# test-board.net
KiCad netlist of a schematic drawn in EAGLE
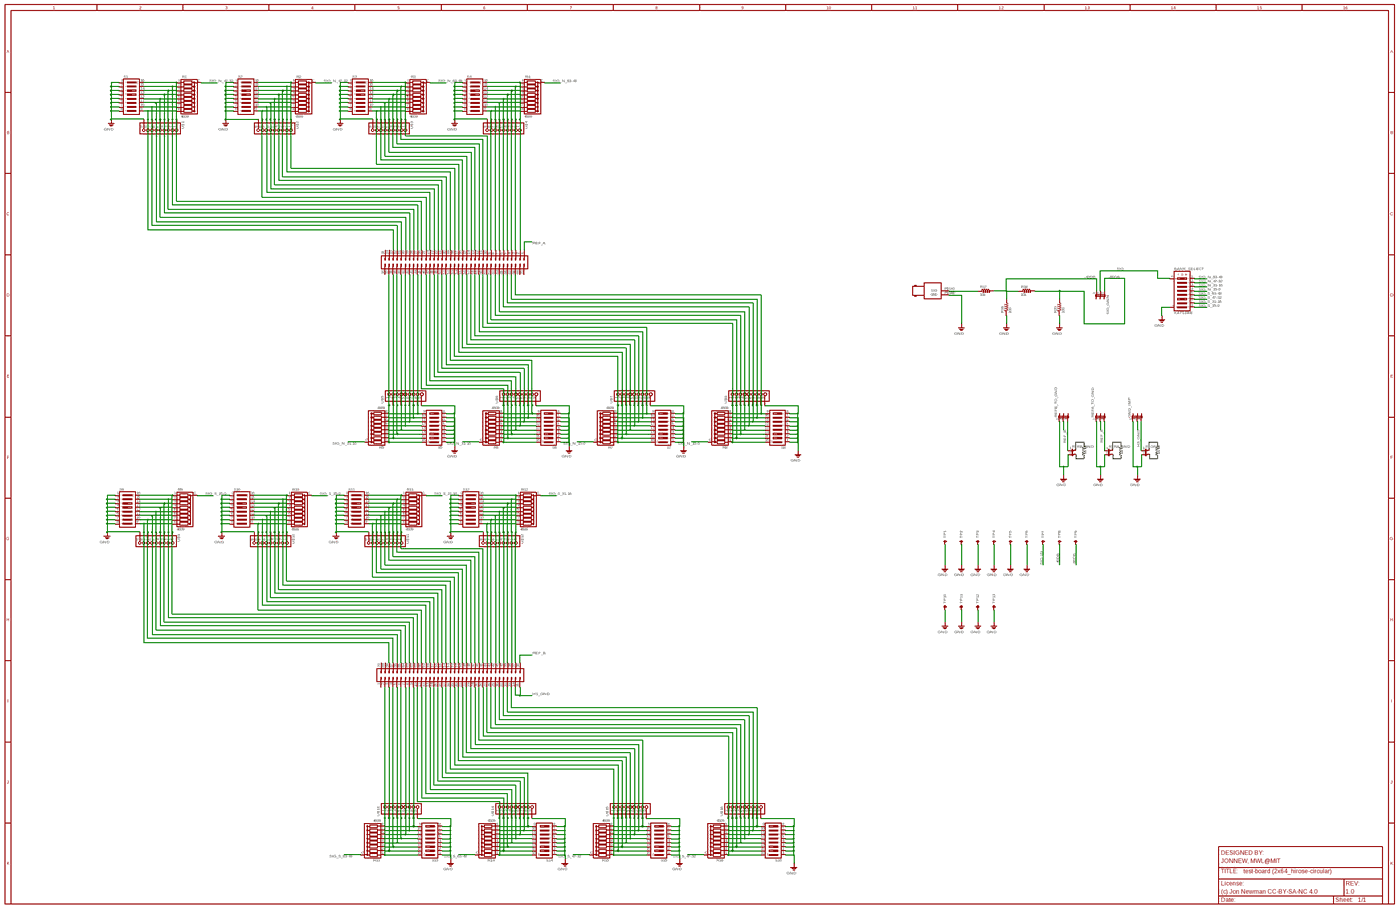
[diagram p0: schematic, sheet 1, overview]
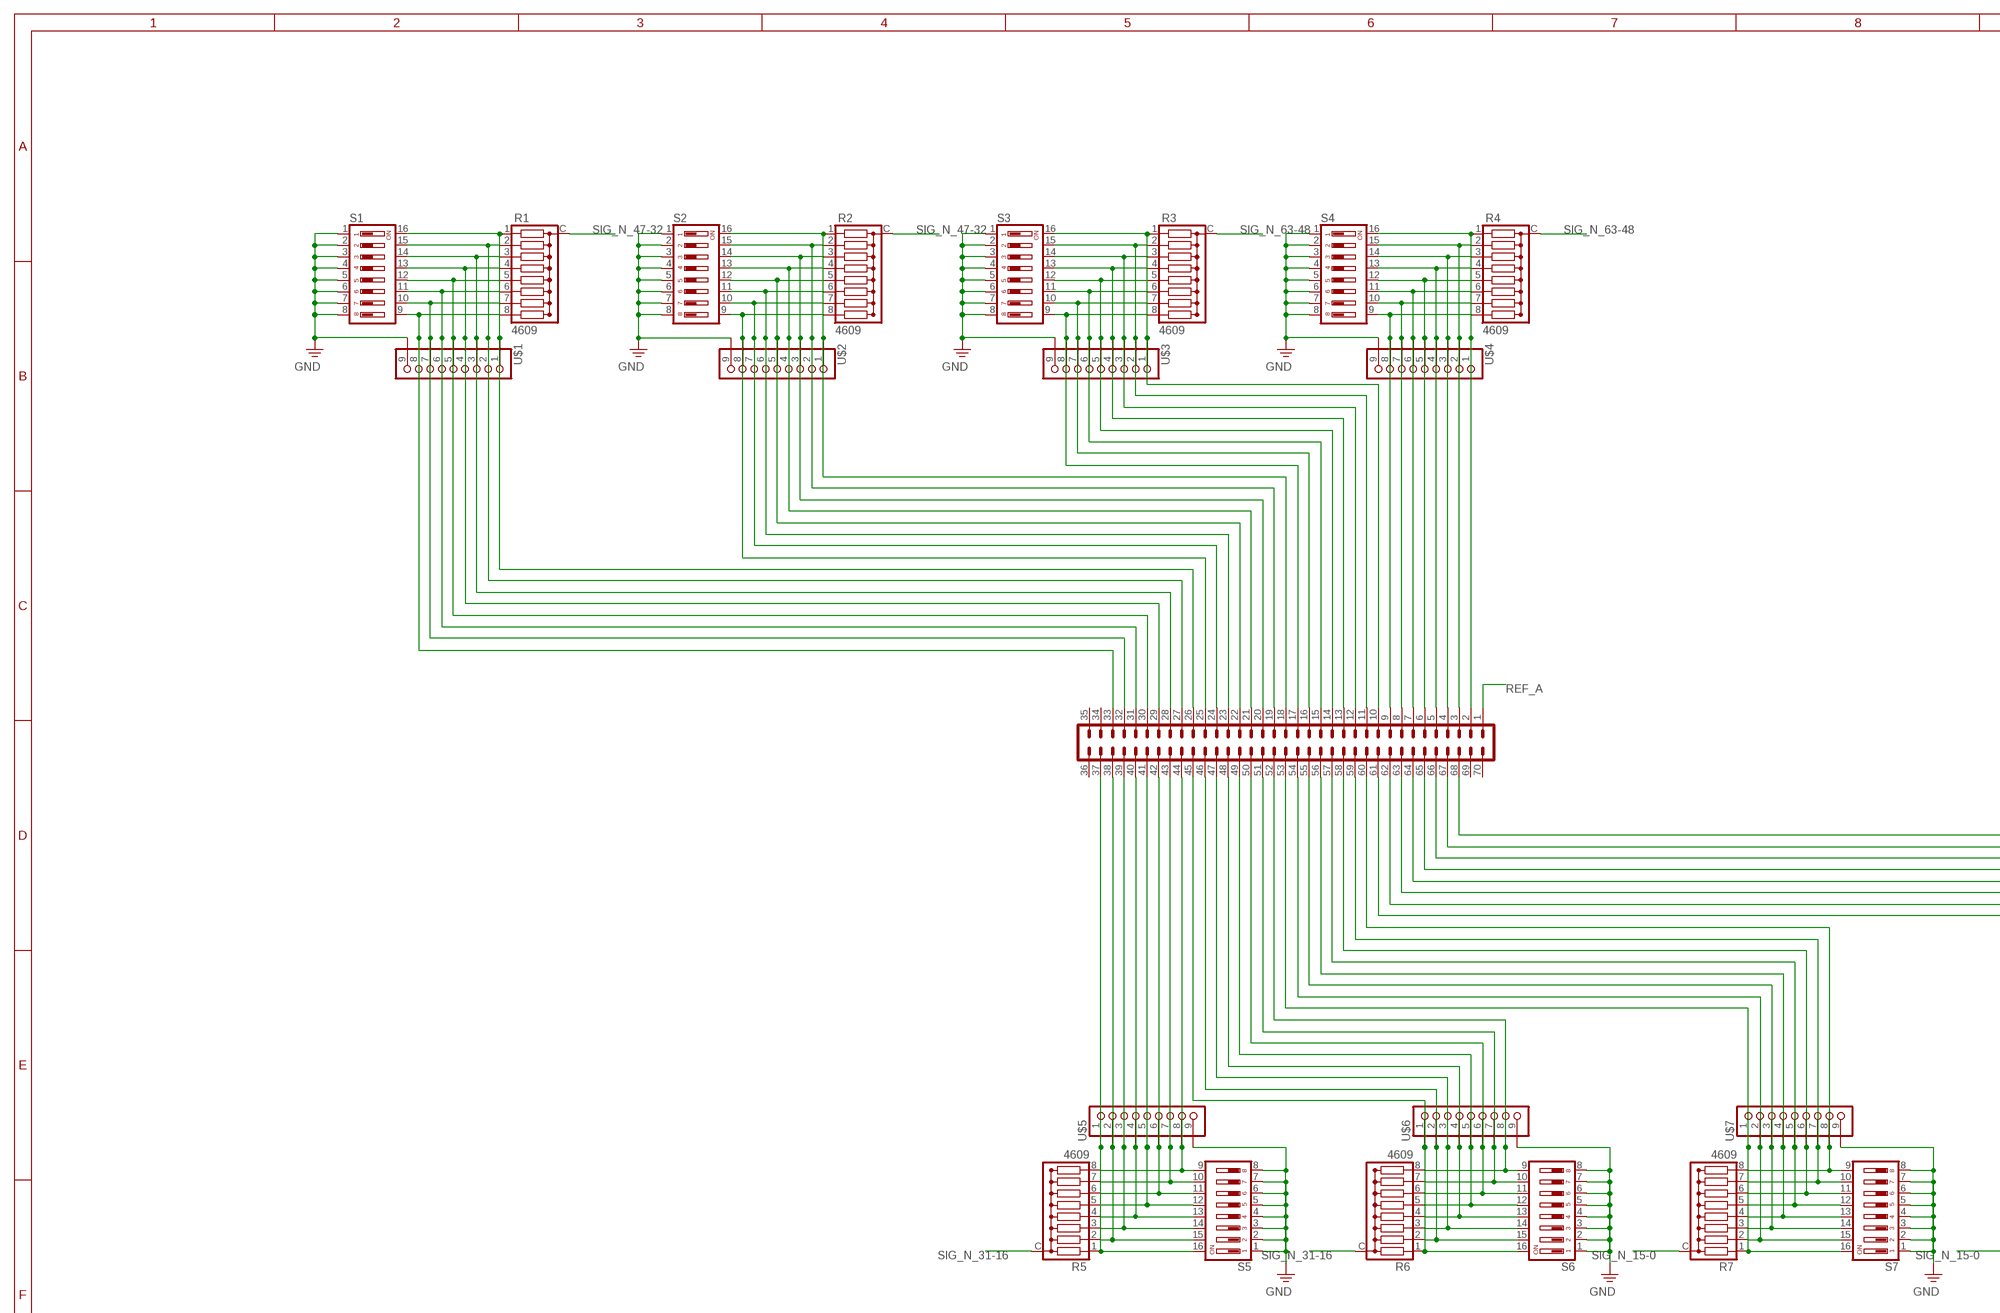
[diagram p1: schematic, sheet 1, part 1 of 4]
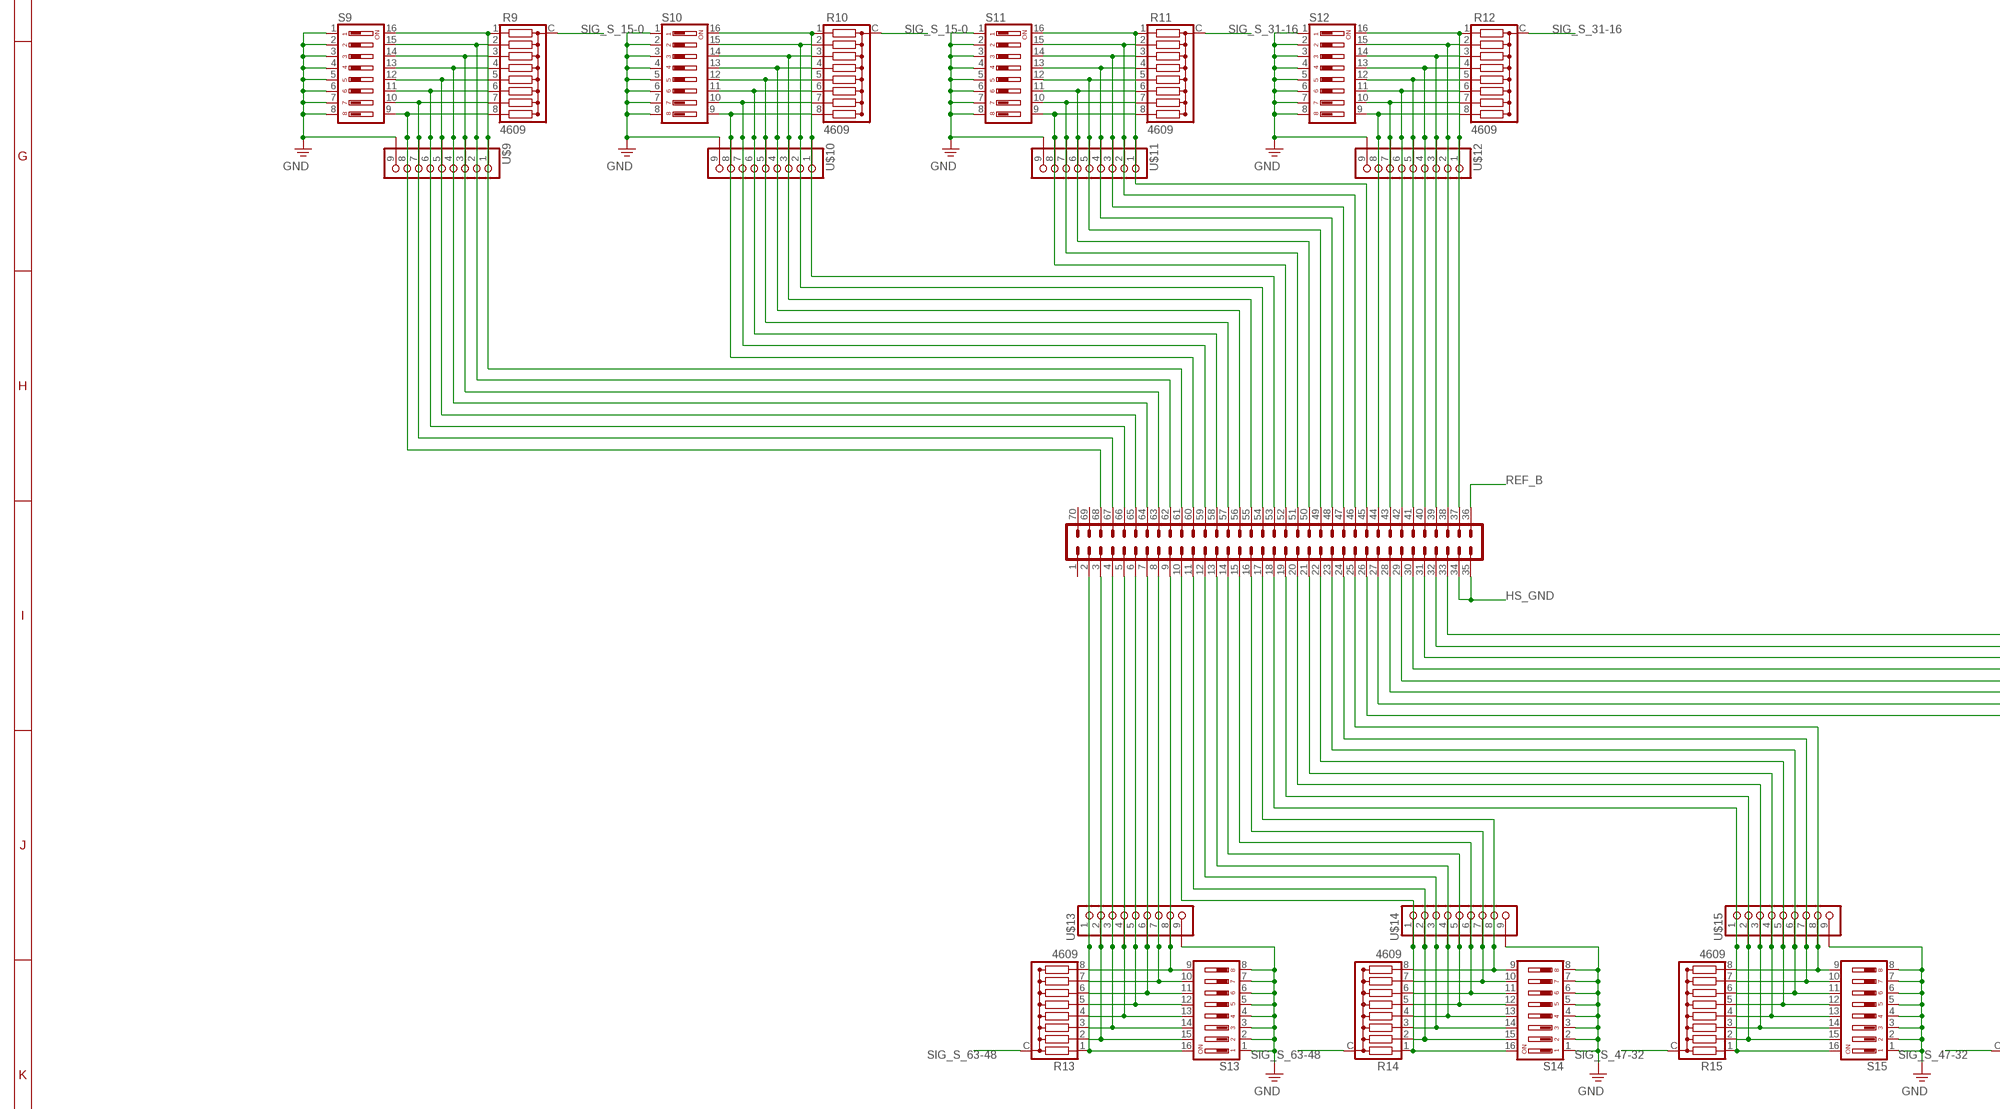
[diagram p2: schematic, sheet 1, part 2 of 4]
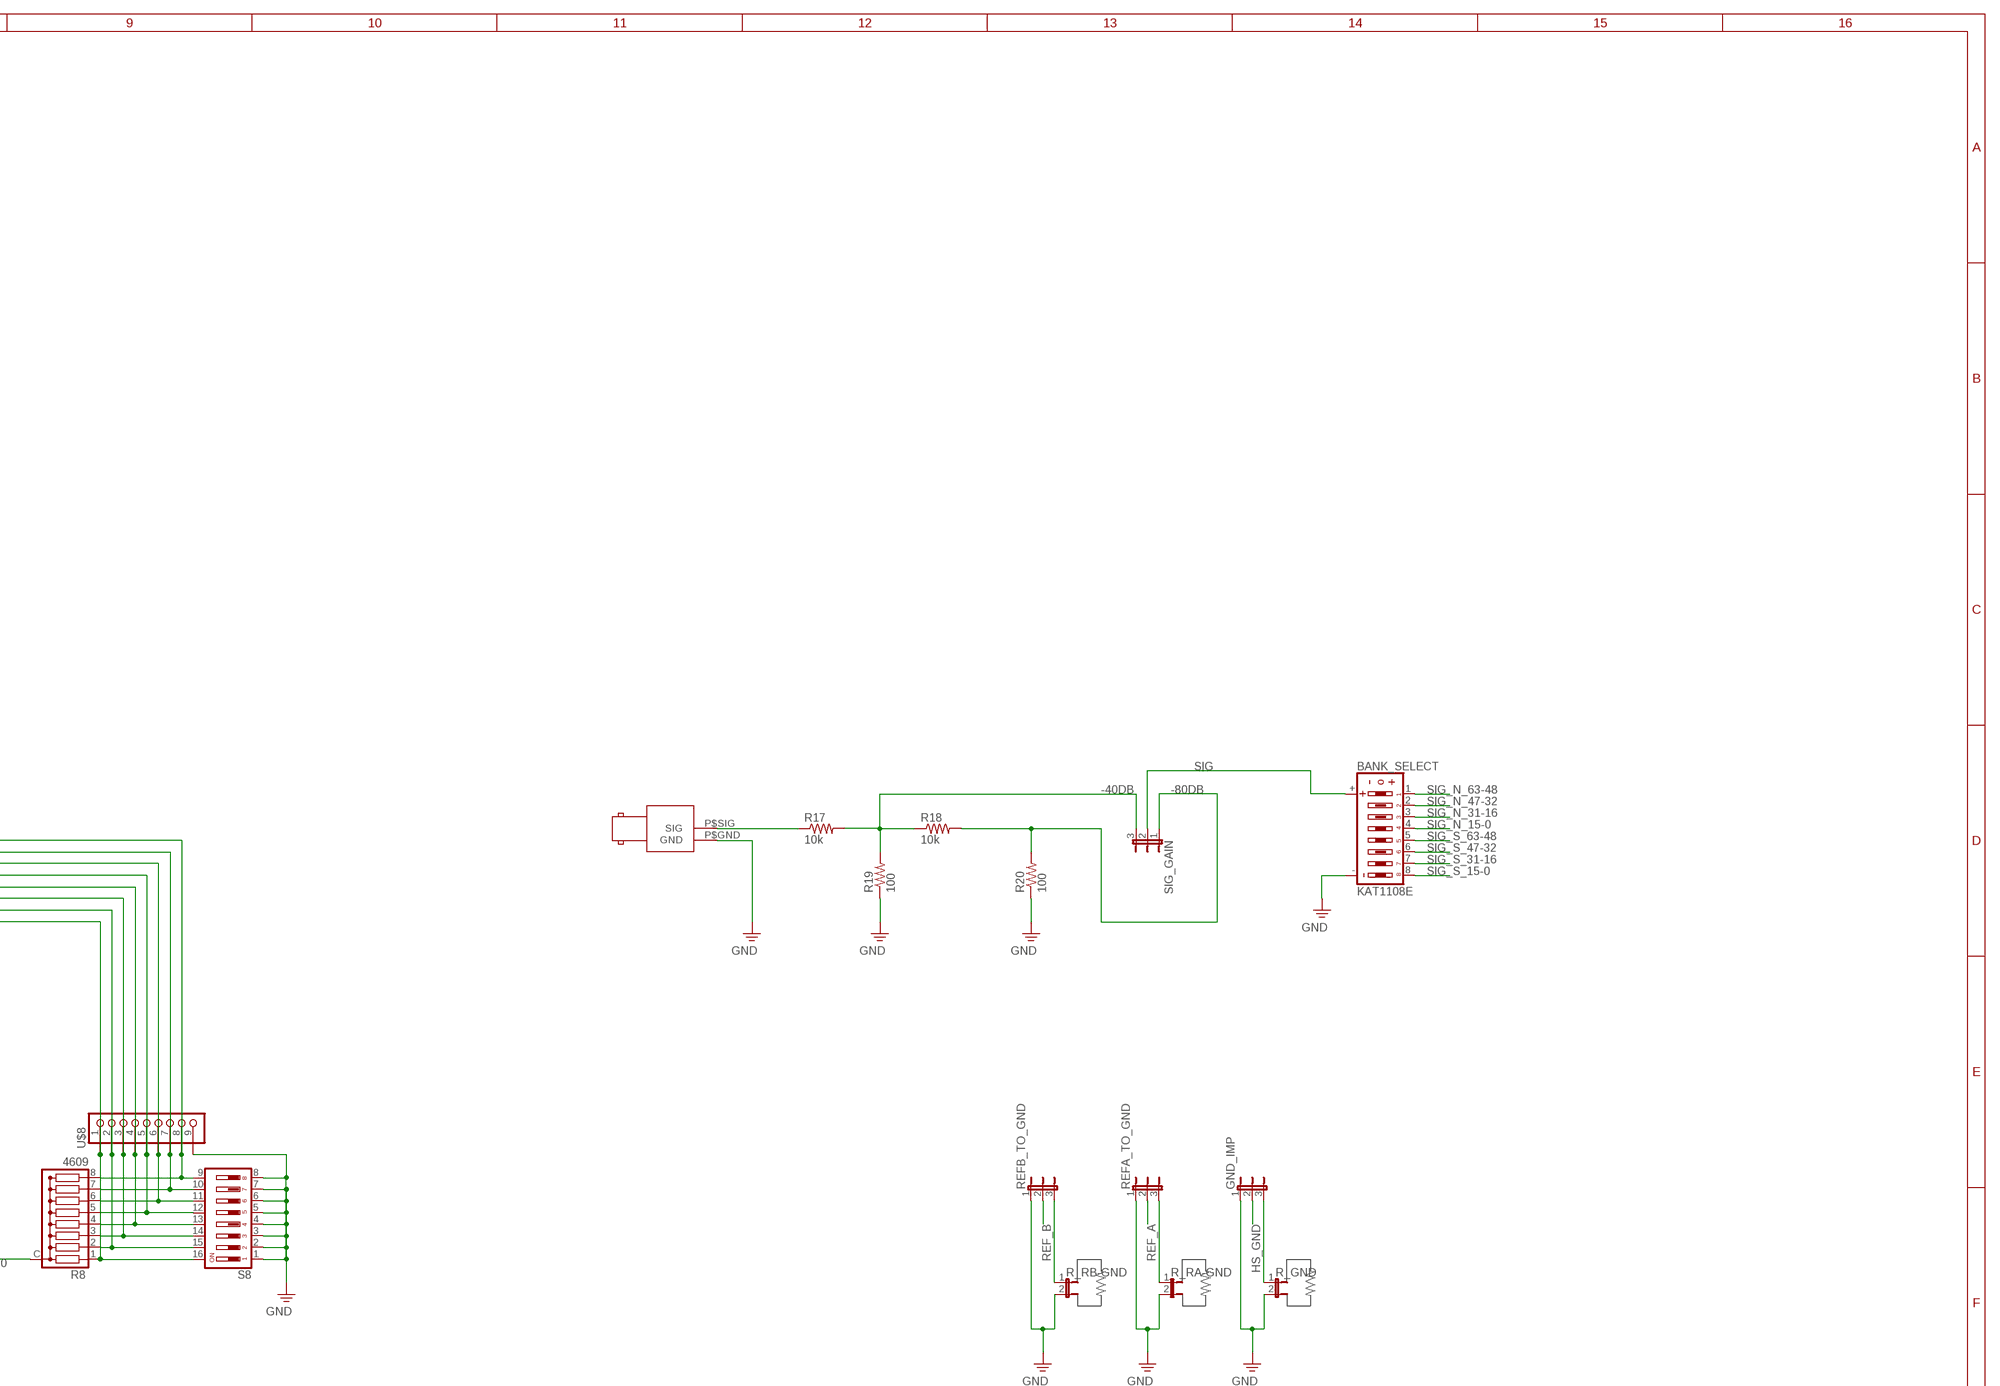
[diagram p3: schematic, sheet 1, part 3 of 4]
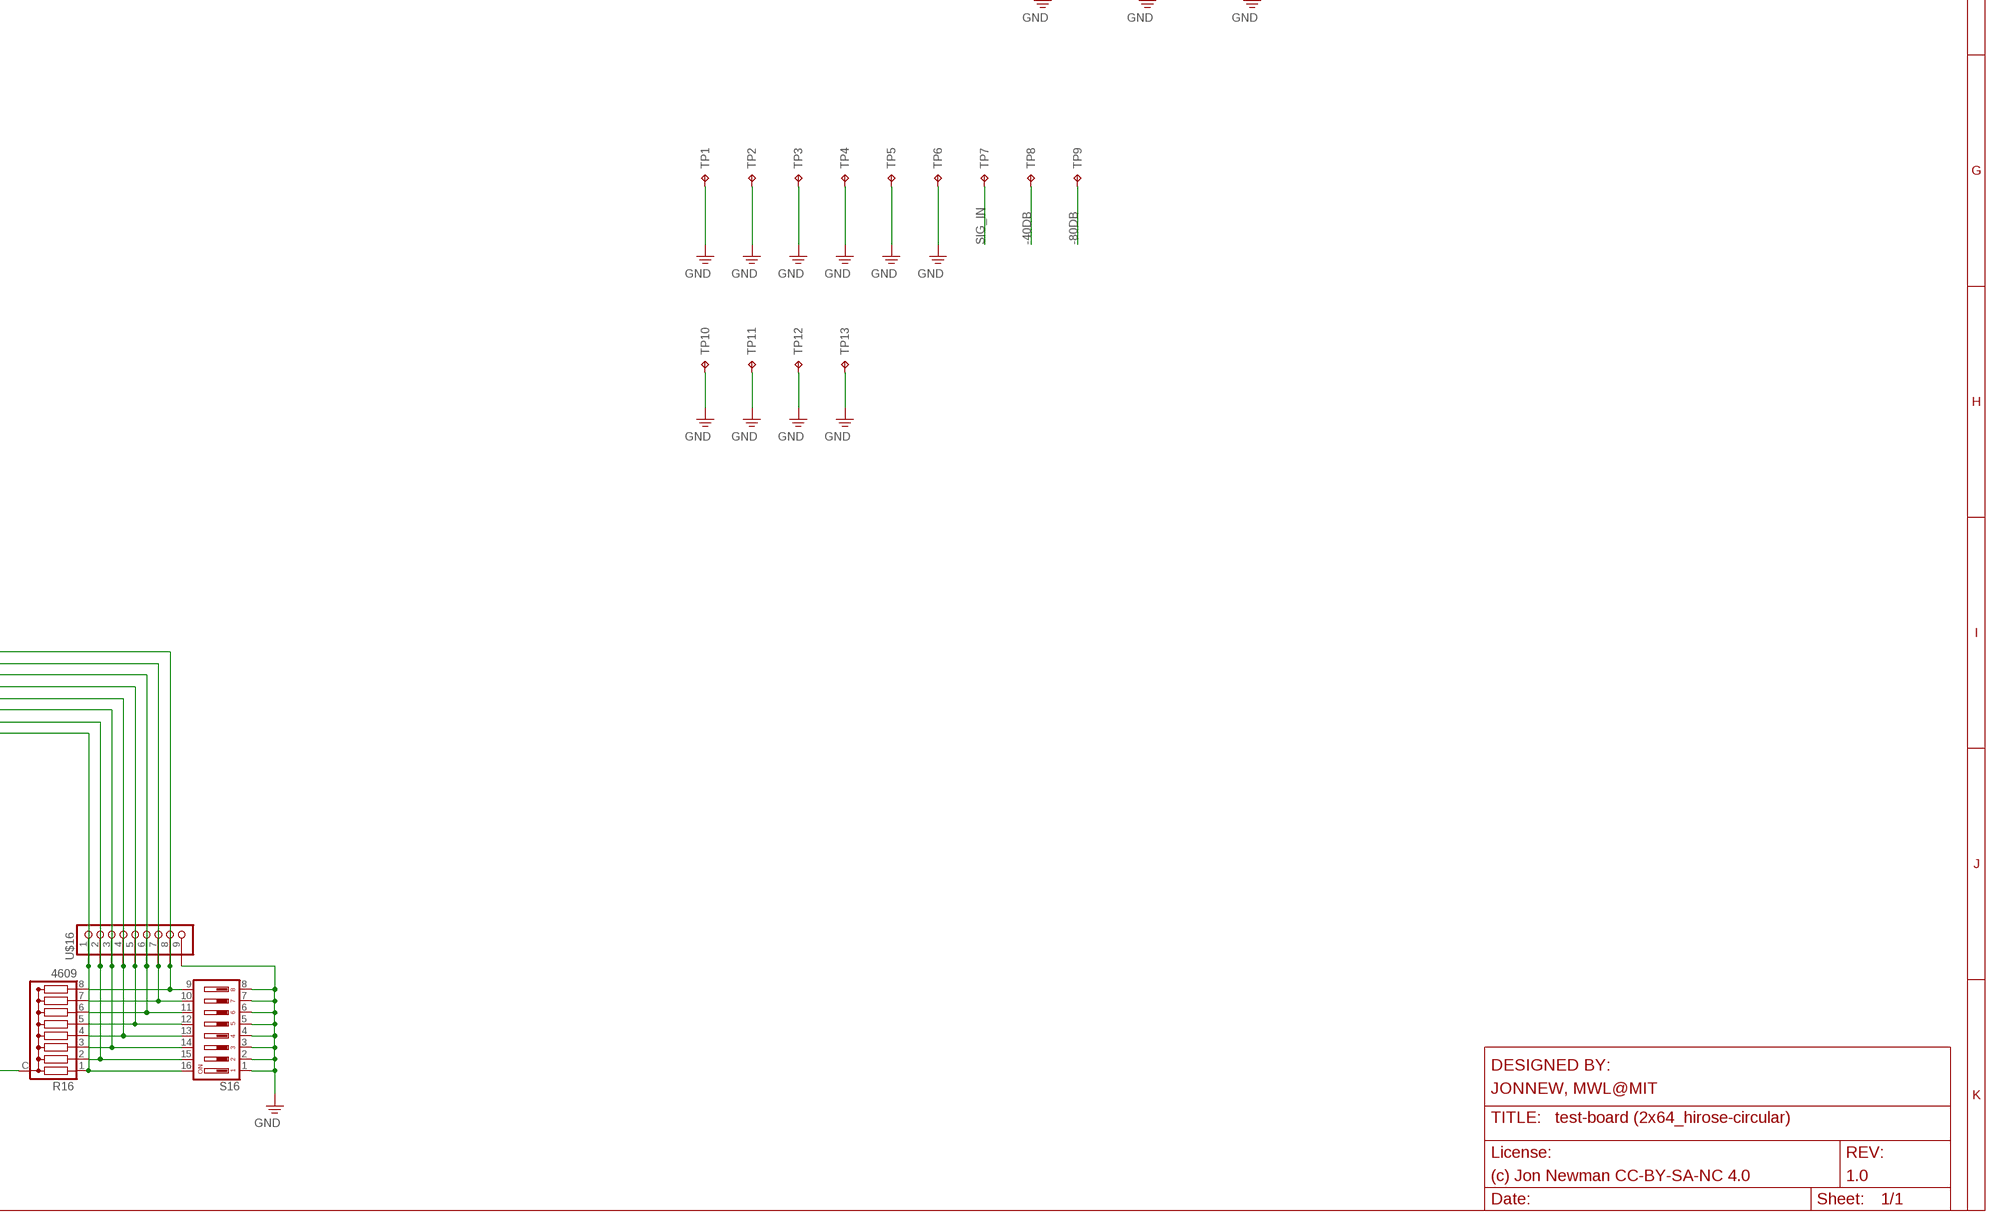
[diagram p4: schematic, sheet 1, part 4 of 4]

(export (version "E")
  (design (tool "Eeschema 10.0.6"))
  (components
    (comp (ref "AIN_N0T")
      (value "DF40HEAD")
      (footprint "eagle-import:DF40-70HEAD")
      (libsource (lib "eagle-import") (part "PINHD-2X35_DF40HEAD"))
    )
    (comp (ref "AIN_S0T")
      (value "DF40HEAD")
      (footprint "eagle-import:DF40-70HEAD")
      (libsource (lib "eagle-import") (part "PINHD-2X35_DF40HEAD"))
    )
    (comp (ref "BANK_SELECT")
      (value "KAT1108E")
      (footprint "eagle-import:206-124_DIP8-SPDT")
      (libsource (lib "eagle-import") (part "DIPSW-008-SPDT_206-124"))
    )
    (comp (ref "GND_IMP")
      (value "JP3E")
      (footprint "eagle-import:JP3")
      (libsource (lib "eagle-import") (part "JP3E"))
    )
    (comp (ref "R1")
      (value "4609")
      (footprint "eagle-import:RNX8-0.1")
      (libsource (lib "eagle-import") (part "RN1X8"))
    )
    (comp (ref "R2")
      (value "4609")
      (footprint "eagle-import:RNX8-0.1")
      (libsource (lib "eagle-import") (part "RN1X8"))
    )
    (comp (ref "R3")
      (value "4609")
      (footprint "eagle-import:RNX8-0.1")
      (libsource (lib "eagle-import") (part "RN1X8"))
    )
    (comp (ref "R4")
      (value "4609")
      (footprint "eagle-import:RNX8-0.1")
      (libsource (lib "eagle-import") (part "RN1X8"))
    )
    (comp (ref "R5")
      (value "4609")
      (footprint "eagle-import:RNX8-0.1")
      (libsource (lib "eagle-import") (part "RN1X8"))
    )
    (comp (ref "R6")
      (value "4609")
      (footprint "eagle-import:RNX8-0.1")
      (libsource (lib "eagle-import") (part "RN1X8"))
    )
    (comp (ref "R7")
      (value "4609")
      (footprint "eagle-import:RNX8-0.1")
      (libsource (lib "eagle-import") (part "RN1X8"))
    )
    (comp (ref "R8")
      (value "4609")
      (footprint "eagle-import:RNX8-0.1")
      (libsource (lib "eagle-import") (part "RN1X8"))
    )
    (comp (ref "R9")
      (value "4609")
      (footprint "eagle-import:RNX8-0.1")
      (libsource (lib "eagle-import") (part "RN1X8"))
    )
    (comp (ref "R10")
      (value "4609")
      (footprint "eagle-import:RNX8-0.1")
      (libsource (lib "eagle-import") (part "RN1X8"))
    )
    (comp (ref "R11")
      (value "4609")
      (footprint "eagle-import:RNX8-0.1")
      (libsource (lib "eagle-import") (part "RN1X8"))
    )
    (comp (ref "R12")
      (value "4609")
      (footprint "eagle-import:RNX8-0.1")
      (libsource (lib "eagle-import") (part "RN1X8"))
    )
    (comp (ref "R13")
      (value "4609")
      (footprint "eagle-import:RNX8-0.1")
      (libsource (lib "eagle-import") (part "RN1X8"))
    )
    (comp (ref "R14")
      (value "4609")
      (footprint "eagle-import:RNX8-0.1")
      (libsource (lib "eagle-import") (part "RN1X8"))
    )
    (comp (ref "R15")
      (value "4609")
      (footprint "eagle-import:RNX8-0.1")
      (libsource (lib "eagle-import") (part "RN1X8"))
    )
    (comp (ref "R16")
      (value "4609")
      (footprint "eagle-import:RNX8-0.1")
      (libsource (lib "eagle-import") (part "RN1X8"))
    )
    (comp (ref "R17")
      (value "10k")
      (footprint "eagle-import:0805")
      (libsource (lib "eagle-import") (part "R_0805"))
    )
    (comp (ref "R18")
      (value "10k")
      (footprint "eagle-import:0805")
      (libsource (lib "eagle-import") (part "R_0805"))
    )
    (comp (ref "R19")
      (value "100")
      (footprint "eagle-import:0805")
      (libsource (lib "eagle-import") (part "R_0805"))
    )
    (comp (ref "R20")
      (value "100")
      (footprint "eagle-import:0805")
      (libsource (lib "eagle-import") (part "R_0805"))
    )
    (comp (ref "REFA_TO_GND")
      (value "JP3E")
      (footprint "eagle-import:JP3")
      (libsource (lib "eagle-import") (part "JP3E"))
    )
    (comp (ref "REFB_TO_GND")
      (value "JP3E")
      (footprint "eagle-import:JP3")
      (libsource (lib "eagle-import") (part "JP3E"))
    )
    (comp (ref "R_GND")
      (value "JP2E_THRU-HOLE")
      (footprint "eagle-import:JP2")
      (libsource (lib "eagle-import") (part "JP2E_THRU-HOLE"))
    )
    (comp (ref "R_RA-GND")
      (value "JP2E_THRU-HOLE")
      (footprint "eagle-import:JP2")
      (libsource (lib "eagle-import") (part "JP2E_THRU-HOLE"))
    )
    (comp (ref "R_RB-GND")
      (value "JP2E_THRU-HOLE")
      (footprint "eagle-import:JP2")
      (libsource (lib "eagle-import") (part "JP2E_THRU-HOLE"))
    )
    (comp (ref "S1")
      (value "DIPSW-008_ADE")
      (footprint "eagle-import:ADE_DIP8-SPST")
      (libsource (lib "eagle-import") (part "DIPSW-008_ADE"))
    )
    (comp (ref "S2")
      (value "DIPSW-008_ADE")
      (footprint "eagle-import:ADE_DIP8-SPST")
      (libsource (lib "eagle-import") (part "DIPSW-008_ADE"))
    )
    (comp (ref "S3")
      (value "DIPSW-008_ADE")
      (footprint "eagle-import:ADE_DIP8-SPST")
      (libsource (lib "eagle-import") (part "DIPSW-008_ADE"))
    )
    (comp (ref "S4")
      (value "DIPSW-008_ADE")
      (footprint "eagle-import:ADE_DIP8-SPST")
      (libsource (lib "eagle-import") (part "DIPSW-008_ADE"))
    )
    (comp (ref "S5")
      (value "DIPSW-008_ADE")
      (footprint "eagle-import:ADE_DIP8-SPST")
      (libsource (lib "eagle-import") (part "DIPSW-008_ADE"))
    )
    (comp (ref "S6")
      (value "DIPSW-008_ADE")
      (footprint "eagle-import:ADE_DIP8-SPST")
      (libsource (lib "eagle-import") (part "DIPSW-008_ADE"))
    )
    (comp (ref "S7")
      (value "DIPSW-008_ADE")
      (footprint "eagle-import:ADE_DIP8-SPST")
      (libsource (lib "eagle-import") (part "DIPSW-008_ADE"))
    )
    (comp (ref "S8")
      (value "DIPSW-008_ADE")
      (footprint "eagle-import:ADE_DIP8-SPST")
      (libsource (lib "eagle-import") (part "DIPSW-008_ADE"))
    )
    (comp (ref "S9")
      (value "DIPSW-008_ADE")
      (footprint "eagle-import:ADE_DIP8-SPST")
      (libsource (lib "eagle-import") (part "DIPSW-008_ADE"))
    )
    (comp (ref "S10")
      (value "DIPSW-008_ADE")
      (footprint "eagle-import:ADE_DIP8-SPST")
      (libsource (lib "eagle-import") (part "DIPSW-008_ADE"))
    )
    (comp (ref "S11")
      (value "DIPSW-008_ADE")
      (footprint "eagle-import:ADE_DIP8-SPST")
      (libsource (lib "eagle-import") (part "DIPSW-008_ADE"))
    )
    (comp (ref "S12")
      (value "DIPSW-008_ADE")
      (footprint "eagle-import:ADE_DIP8-SPST")
      (libsource (lib "eagle-import") (part "DIPSW-008_ADE"))
    )
    (comp (ref "S13")
      (value "DIPSW-008_ADE")
      (footprint "eagle-import:ADE_DIP8-SPST")
      (libsource (lib "eagle-import") (part "DIPSW-008_ADE"))
    )
    (comp (ref "S14")
      (value "DIPSW-008_ADE")
      (footprint "eagle-import:ADE_DIP8-SPST")
      (libsource (lib "eagle-import") (part "DIPSW-008_ADE"))
    )
    (comp (ref "S15")
      (value "DIPSW-008_ADE")
      (footprint "eagle-import:ADE_DIP8-SPST")
      (libsource (lib "eagle-import") (part "DIPSW-008_ADE"))
    )
    (comp (ref "S16")
      (value "DIPSW-008_ADE")
      (footprint "eagle-import:ADE_DIP8-SPST")
      (libsource (lib "eagle-import") (part "DIPSW-008_ADE"))
    )
    (comp (ref "SIG_GAIN")
      (value "JP3E")
      (footprint "eagle-import:JP3")
      (libsource (lib "eagle-import") (part "JP3E"))
    )
    (comp (ref "SIG_IN")
      (value "1-1634622-0")
      (footprint "eagle-import:BNC_RIGHT_ANGLE")
      (libsource (lib "eagle-import") (part "BNC_RIGHT_ANGLE"))
    )
    (comp (ref "TP1")
      (value "GND")
      (footprint "eagle-import:P1-20")
      (libsource (lib "eagle-import") (part "TPPAD1-20"))
    )
    (comp (ref "TP2")
      (value "GND")
      (footprint "eagle-import:P1-20")
      (libsource (lib "eagle-import") (part "TPPAD1-20"))
    )
    (comp (ref "TP3")
      (value "GND")
      (footprint "eagle-import:P1-20")
      (libsource (lib "eagle-import") (part "TPPAD1-20"))
    )
    (comp (ref "TP4")
      (value "GND")
      (footprint "eagle-import:P1-20")
      (libsource (lib "eagle-import") (part "TPPAD1-20"))
    )
    (comp (ref "TP5")
      (value "GND")
      (footprint "eagle-import:P1-20")
      (libsource (lib "eagle-import") (part "TPPAD1-20"))
    )
    (comp (ref "TP6")
      (value "GND")
      (footprint "eagle-import:P1-20")
      (libsource (lib "eagle-import") (part "TPPAD1-20"))
    )
    (comp (ref "TP7")
      (value "SIG_IN")
      (footprint "eagle-import:P1-20")
      (libsource (lib "eagle-import") (part "TPPAD1-20"))
    )
    (comp (ref "TP8")
      (value "-40dB")
      (footprint "eagle-import:P1-20")
      (libsource (lib "eagle-import") (part "TPPAD1-20"))
    )
    (comp (ref "TP9")
      (value "-80dB")
      (footprint "eagle-import:P1-20")
      (libsource (lib "eagle-import") (part "TPPAD1-20"))
    )
    (comp (ref "TP10")
      (value "TP_4-40")
      (footprint "eagle-import:4-40_PLATED")
      (libsource (lib "eagle-import") (part "TP_4-40"))
    )
    (comp (ref "TP11")
      (value "TP_4-40")
      (footprint "eagle-import:4-40_PLATED")
      (libsource (lib "eagle-import") (part "TP_4-40"))
    )
    (comp (ref "TP12")
      (value "TP_4-40")
      (footprint "eagle-import:4-40_PLATED")
      (libsource (lib "eagle-import") (part "TP_4-40"))
    )
    (comp (ref "TP13")
      (value "TP_4-40")
      (footprint "eagle-import:4-40_PLATED")
      (libsource (lib "eagle-import") (part "TP_4-40"))
    )
    (comp (ref "U$1")
      (value "PINHD-1X9")
      (footprint "eagle-import:1X09")
      (libsource (lib "eagle-import") (part "PINHD-1X9"))
    )
    (comp (ref "U$2")
      (value "PINHD-1X9")
      (footprint "eagle-import:1X09")
      (libsource (lib "eagle-import") (part "PINHD-1X9"))
    )
    (comp (ref "U$3")
      (value "PINHD-1X9")
      (footprint "eagle-import:1X09")
      (libsource (lib "eagle-import") (part "PINHD-1X9"))
    )
    (comp (ref "U$4")
      (value "PINHD-1X9")
      (footprint "eagle-import:1X09")
      (libsource (lib "eagle-import") (part "PINHD-1X9"))
    )
    (comp (ref "U$5")
      (value "PINHD-1X9")
      (footprint "eagle-import:1X09")
      (libsource (lib "eagle-import") (part "PINHD-1X9"))
    )
    (comp (ref "U$6")
      (value "PINHD-1X9")
      (footprint "eagle-import:1X09")
      (libsource (lib "eagle-import") (part "PINHD-1X9"))
    )
    (comp (ref "U$7")
      (value "PINHD-1X9")
      (footprint "eagle-import:1X09")
      (libsource (lib "eagle-import") (part "PINHD-1X9"))
    )
    (comp (ref "U$8")
      (value "PINHD-1X9")
      (footprint "eagle-import:1X09")
      (libsource (lib "eagle-import") (part "PINHD-1X9"))
    )
    (comp (ref "U$9")
      (value "PINHD-1X9")
      (footprint "eagle-import:1X09")
      (libsource (lib "eagle-import") (part "PINHD-1X9"))
    )
    (comp (ref "U$10")
      (value "PINHD-1X9")
      (footprint "eagle-import:1X09")
      (libsource (lib "eagle-import") (part "PINHD-1X9"))
    )
    (comp (ref "U$11")
      (value "PINHD-1X9")
      (footprint "eagle-import:1X09")
      (libsource (lib "eagle-import") (part "PINHD-1X9"))
    )
    (comp (ref "U$12")
      (value "PINHD-1X9")
      (footprint "eagle-import:1X09")
      (libsource (lib "eagle-import") (part "PINHD-1X9"))
    )
    (comp (ref "U$13")
      (value "PINHD-1X9")
      (footprint "eagle-import:1X09")
      (libsource (lib "eagle-import") (part "PINHD-1X9"))
    )
    (comp (ref "U$14")
      (value "PINHD-1X9")
      (footprint "eagle-import:1X09")
      (libsource (lib "eagle-import") (part "PINHD-1X9"))
    )
    (comp (ref "U$15")
      (value "PINHD-1X9")
      (footprint "eagle-import:1X09")
      (libsource (lib "eagle-import") (part "PINHD-1X9"))
    )
    (comp (ref "U$16")
      (value "PINHD-1X9")
      (footprint "eagle-import:1X09")
      (libsource (lib "eagle-import") (part "PINHD-1X9"))
    )
  )
  (nets
    (net (code "1") (name "/-40DB") (class "Default")
      (node (ref "R17") (pin "2") (pinfunction "2_2") (pintype "passive"))
      (node (ref "R18") (pin "1") (pinfunction "1_1") (pintype "passive"))
      (node (ref "R19") (pin "2") (pinfunction "2_2") (pintype "passive"))
      (node (ref "SIG_GAIN") (pin "3") (pinfunction "3_3") (pintype "passive"))
      (node (ref "TP8") (pin "TP") (pinfunction "TP_TP") (pintype "input"))
    )
    (net (code "2") (name "/-80DB") (class "Default")
      (node (ref "R18") (pin "2") (pinfunction "2_2") (pintype "passive"))
      (node (ref "R20") (pin "2") (pinfunction "2_2") (pintype "passive"))
      (node (ref "SIG_GAIN") (pin "1") (pinfunction "1_1") (pintype "passive"))
      (node (ref "TP9") (pin "TP") (pinfunction "TP_TP") (pintype "input"))
    )
    (net (code "3") (name "/HS_GND") (class "Default")
      (node (ref "AIN_S0T") (pin "34") (pinfunction "34_34") (pintype "bidirectional"))
      (node (ref "AIN_S0T") (pin "35") (pinfunction "35_35") (pintype "bidirectional"))
      (node (ref "GND_IMP") (pin "2") (pinfunction "2_2") (pintype "passive"))
    )
    (net (code "4") (name "/REF_A") (class "Default")
      (node (ref "AIN_N0T") (pin "1") (pinfunction "1_1") (pintype "bidirectional"))
      (node (ref "REFA_TO_GND") (pin "2") (pinfunction "2_2") (pintype "passive"))
    )
    (net (code "5") (name "/REF_B") (class "Default")
      (node (ref "AIN_S0T") (pin "36") (pinfunction "36_36") (pintype "bidirectional"))
      (node (ref "REFB_TO_GND") (pin "2") (pinfunction "2_2") (pintype "passive"))
    )
    (net (code "6") (name "/SIG") (class "Default")
      (node (ref "BANK_SELECT") (pin "+") (pinfunction "+_+") (pintype "passive"))
      (node (ref "SIG_GAIN") (pin "2") (pinfunction "2_2") (pintype "passive"))
    )
    (net (code "7") (name "/SIG_IN") (class "Default")
      (node (ref "R17") (pin "1") (pinfunction "1_1") (pintype "passive"))
      (node (ref "SIG_IN") (pin "P$SIG") (pinfunction "SIG_P$SIG") (pintype "bidirectional"))
      (node (ref "TP7") (pin "TP") (pinfunction "TP_TP") (pintype "input"))
    )
    (net (code "8") (name "/SIG_N_15-0") (class "Default")
      (node (ref "BANK_SELECT") (pin "4") (pinfunction "4_4") (pintype "passive"))
      (node (ref "R7") (pin "C") (pinfunction "C_C") (pintype "passive"))
      (node (ref "R8") (pin "C") (pinfunction "C_C") (pintype "passive"))
    )
    (net (code "9") (name "/SIG_N_31-16") (class "Default")
      (node (ref "BANK_SELECT") (pin "3") (pinfunction "3_3") (pintype "passive"))
      (node (ref "R5") (pin "C") (pinfunction "C_C") (pintype "passive"))
      (node (ref "R6") (pin "C") (pinfunction "C_C") (pintype "passive"))
    )
    (net (code "10") (name "/SIG_N_47-32") (class "Default")
      (node (ref "BANK_SELECT") (pin "2") (pinfunction "2_2") (pintype "passive"))
      (node (ref "R1") (pin "C") (pinfunction "C_C") (pintype "passive"))
      (node (ref "R2") (pin "C") (pinfunction "C_C") (pintype "passive"))
    )
    (net (code "11") (name "/SIG_N_63-48") (class "Default")
      (node (ref "BANK_SELECT") (pin "1") (pinfunction "1_1") (pintype "passive"))
      (node (ref "R3") (pin "C") (pinfunction "C_C") (pintype "passive"))
      (node (ref "R4") (pin "C") (pinfunction "C_C") (pintype "passive"))
    )
    (net (code "12") (name "/SIG_S_15-0") (class "Default")
      (node (ref "BANK_SELECT") (pin "8") (pinfunction "8_8") (pintype "passive"))
      (node (ref "R10") (pin "C") (pinfunction "C_C") (pintype "passive"))
      (node (ref "R9") (pin "C") (pinfunction "C_C") (pintype "passive"))
    )
    (net (code "13") (name "/SIG_S_31-16") (class "Default")
      (node (ref "BANK_SELECT") (pin "7") (pinfunction "7_7") (pintype "passive"))
      (node (ref "R11") (pin "C") (pinfunction "C_C") (pintype "passive"))
      (node (ref "R12") (pin "C") (pinfunction "C_C") (pintype "passive"))
    )
    (net (code "14") (name "/SIG_S_47-32") (class "Default")
      (node (ref "BANK_SELECT") (pin "6") (pinfunction "6_6") (pintype "passive"))
      (node (ref "R15") (pin "C") (pinfunction "C_C") (pintype "passive"))
      (node (ref "R16") (pin "C") (pinfunction "C_C") (pintype "passive"))
    )
    (net (code "15") (name "/SIG_S_63-48") (class "Default")
      (node (ref "BANK_SELECT") (pin "5") (pinfunction "5_5") (pintype "passive"))
      (node (ref "R13") (pin "C") (pinfunction "C_C") (pintype "passive"))
      (node (ref "R14") (pin "C") (pinfunction "C_C") (pintype "passive"))
    )
    (net (code "16") (name "GND") (class "Default")
      (node (ref "BANK_SELECT") (pin "-") (pinfunction "-_-") (pintype "passive"))
      (node (ref "GND_IMP") (pin "1") (pinfunction "1_1") (pintype "passive"))
      (node (ref "R19") (pin "1") (pinfunction "1_1") (pintype "passive"))
      (node (ref "R20") (pin "1") (pinfunction "1_1") (pintype "passive"))
      (node (ref "REFA_TO_GND") (pin "1") (pinfunction "1_1") (pintype "passive"))
      (node (ref "REFB_TO_GND") (pin "1") (pinfunction "1_1") (pintype "passive"))
      (node (ref "R_GND") (pin "2") (pinfunction "2_2") (pintype "passive"))
      (node (ref "R_RA-GND") (pin "2") (pinfunction "2_2") (pintype "passive"))
      (node (ref "R_RB-GND") (pin "2") (pinfunction "2_2") (pintype "passive"))
      (node (ref "S1") (pin "1") (pinfunction "1_1") (pintype "passive"))
      (node (ref "S1") (pin "2") (pinfunction "2_2") (pintype "passive"))
      (node (ref "S1") (pin "3") (pinfunction "3_3") (pintype "passive"))
      (node (ref "S1") (pin "4") (pinfunction "4_4") (pintype "passive"))
      (node (ref "S1") (pin "5") (pinfunction "5_5") (pintype "passive"))
      (node (ref "S1") (pin "6") (pinfunction "6_6") (pintype "passive"))
      (node (ref "S1") (pin "7") (pinfunction "7_7") (pintype "passive"))
      (node (ref "S1") (pin "8") (pinfunction "8_8") (pintype "passive"))
      (node (ref "S10") (pin "1") (pinfunction "1_1") (pintype "passive"))
      (node (ref "S10") (pin "2") (pinfunction "2_2") (pintype "passive"))
      (node (ref "S10") (pin "3") (pinfunction "3_3") (pintype "passive"))
      (node (ref "S10") (pin "4") (pinfunction "4_4") (pintype "passive"))
      (node (ref "S10") (pin "5") (pinfunction "5_5") (pintype "passive"))
      (node (ref "S10") (pin "6") (pinfunction "6_6") (pintype "passive"))
      (node (ref "S10") (pin "7") (pinfunction "7_7") (pintype "passive"))
      (node (ref "S10") (pin "8") (pinfunction "8_8") (pintype "passive"))
      (node (ref "S11") (pin "1") (pinfunction "1_1") (pintype "passive"))
      (node (ref "S11") (pin "2") (pinfunction "2_2") (pintype "passive"))
      (node (ref "S11") (pin "3") (pinfunction "3_3") (pintype "passive"))
      (node (ref "S11") (pin "4") (pinfunction "4_4") (pintype "passive"))
      (node (ref "S11") (pin "5") (pinfunction "5_5") (pintype "passive"))
      (node (ref "S11") (pin "6") (pinfunction "6_6") (pintype "passive"))
      (node (ref "S11") (pin "7") (pinfunction "7_7") (pintype "passive"))
      (node (ref "S11") (pin "8") (pinfunction "8_8") (pintype "passive"))
      (node (ref "S12") (pin "1") (pinfunction "1_1") (pintype "passive"))
      (node (ref "S12") (pin "2") (pinfunction "2_2") (pintype "passive"))
      (node (ref "S12") (pin "3") (pinfunction "3_3") (pintype "passive"))
      (node (ref "S12") (pin "4") (pinfunction "4_4") (pintype "passive"))
      (node (ref "S12") (pin "5") (pinfunction "5_5") (pintype "passive"))
      (node (ref "S12") (pin "6") (pinfunction "6_6") (pintype "passive"))
      (node (ref "S12") (pin "7") (pinfunction "7_7") (pintype "passive"))
      (node (ref "S12") (pin "8") (pinfunction "8_8") (pintype "passive"))
      (node (ref "S13") (pin "1") (pinfunction "1_1") (pintype "passive"))
      (node (ref "S13") (pin "2") (pinfunction "2_2") (pintype "passive"))
      (node (ref "S13") (pin "3") (pinfunction "3_3") (pintype "passive"))
      (node (ref "S13") (pin "4") (pinfunction "4_4") (pintype "passive"))
      (node (ref "S13") (pin "5") (pinfunction "5_5") (pintype "passive"))
      (node (ref "S13") (pin "6") (pinfunction "6_6") (pintype "passive"))
      (node (ref "S13") (pin "7") (pinfunction "7_7") (pintype "passive"))
      (node (ref "S13") (pin "8") (pinfunction "8_8") (pintype "passive"))
      (node (ref "S14") (pin "1") (pinfunction "1_1") (pintype "passive"))
      (node (ref "S14") (pin "2") (pinfunction "2_2") (pintype "passive"))
      (node (ref "S14") (pin "3") (pinfunction "3_3") (pintype "passive"))
      (node (ref "S14") (pin "4") (pinfunction "4_4") (pintype "passive"))
      (node (ref "S14") (pin "5") (pinfunction "5_5") (pintype "passive"))
      (node (ref "S14") (pin "6") (pinfunction "6_6") (pintype "passive"))
      (node (ref "S14") (pin "7") (pinfunction "7_7") (pintype "passive"))
      (node (ref "S14") (pin "8") (pinfunction "8_8") (pintype "passive"))
      (node (ref "S15") (pin "1") (pinfunction "1_1") (pintype "passive"))
      (node (ref "S15") (pin "2") (pinfunction "2_2") (pintype "passive"))
      (node (ref "S15") (pin "3") (pinfunction "3_3") (pintype "passive"))
      (node (ref "S15") (pin "4") (pinfunction "4_4") (pintype "passive"))
      (node (ref "S15") (pin "5") (pinfunction "5_5") (pintype "passive"))
      (node (ref "S15") (pin "6") (pinfunction "6_6") (pintype "passive"))
      (node (ref "S15") (pin "7") (pinfunction "7_7") (pintype "passive"))
      (node (ref "S15") (pin "8") (pinfunction "8_8") (pintype "passive"))
      (node (ref "S16") (pin "1") (pinfunction "1_1") (pintype "passive"))
      (node (ref "S16") (pin "2") (pinfunction "2_2") (pintype "passive"))
      (node (ref "S16") (pin "3") (pinfunction "3_3") (pintype "passive"))
      (node (ref "S16") (pin "4") (pinfunction "4_4") (pintype "passive"))
      (node (ref "S16") (pin "5") (pinfunction "5_5") (pintype "passive"))
      (node (ref "S16") (pin "6") (pinfunction "6_6") (pintype "passive"))
      (node (ref "S16") (pin "7") (pinfunction "7_7") (pintype "passive"))
      (node (ref "S16") (pin "8") (pinfunction "8_8") (pintype "passive"))
      (node (ref "S2") (pin "1") (pinfunction "1_1") (pintype "passive"))
      (node (ref "S2") (pin "2") (pinfunction "2_2") (pintype "passive"))
      (node (ref "S2") (pin "3") (pinfunction "3_3") (pintype "passive"))
      (node (ref "S2") (pin "4") (pinfunction "4_4") (pintype "passive"))
      (node (ref "S2") (pin "5") (pinfunction "5_5") (pintype "passive"))
      (node (ref "S2") (pin "6") (pinfunction "6_6") (pintype "passive"))
      (node (ref "S2") (pin "7") (pinfunction "7_7") (pintype "passive"))
      (node (ref "S2") (pin "8") (pinfunction "8_8") (pintype "passive"))
      (node (ref "S3") (pin "1") (pinfunction "1_1") (pintype "passive"))
      (node (ref "S3") (pin "2") (pinfunction "2_2") (pintype "passive"))
      (node (ref "S3") (pin "3") (pinfunction "3_3") (pintype "passive"))
      (node (ref "S3") (pin "4") (pinfunction "4_4") (pintype "passive"))
      (node (ref "S3") (pin "5") (pinfunction "5_5") (pintype "passive"))
      (node (ref "S3") (pin "6") (pinfunction "6_6") (pintype "passive"))
      (node (ref "S3") (pin "7") (pinfunction "7_7") (pintype "passive"))
      (node (ref "S3") (pin "8") (pinfunction "8_8") (pintype "passive"))
      (node (ref "S4") (pin "1") (pinfunction "1_1") (pintype "passive"))
      (node (ref "S4") (pin "2") (pinfunction "2_2") (pintype "passive"))
      (node (ref "S4") (pin "3") (pinfunction "3_3") (pintype "passive"))
      (node (ref "S4") (pin "4") (pinfunction "4_4") (pintype "passive"))
      (node (ref "S4") (pin "5") (pinfunction "5_5") (pintype "passive"))
      (node (ref "S4") (pin "6") (pinfunction "6_6") (pintype "passive"))
      (node (ref "S4") (pin "7") (pinfunction "7_7") (pintype "passive"))
      (node (ref "S4") (pin "8") (pinfunction "8_8") (pintype "passive"))
      (node (ref "S5") (pin "1") (pinfunction "1_1") (pintype "passive"))
      (node (ref "S5") (pin "2") (pinfunction "2_2") (pintype "passive"))
      (node (ref "S5") (pin "3") (pinfunction "3_3") (pintype "passive"))
      (node (ref "S5") (pin "4") (pinfunction "4_4") (pintype "passive"))
      (node (ref "S5") (pin "5") (pinfunction "5_5") (pintype "passive"))
      (node (ref "S5") (pin "6") (pinfunction "6_6") (pintype "passive"))
      (node (ref "S5") (pin "7") (pinfunction "7_7") (pintype "passive"))
      (node (ref "S5") (pin "8") (pinfunction "8_8") (pintype "passive"))
      (node (ref "S6") (pin "1") (pinfunction "1_1") (pintype "passive"))
      (node (ref "S6") (pin "2") (pinfunction "2_2") (pintype "passive"))
      (node (ref "S6") (pin "3") (pinfunction "3_3") (pintype "passive"))
      (node (ref "S6") (pin "4") (pinfunction "4_4") (pintype "passive"))
      (node (ref "S6") (pin "5") (pinfunction "5_5") (pintype "passive"))
      (node (ref "S6") (pin "6") (pinfunction "6_6") (pintype "passive"))
      (node (ref "S6") (pin "7") (pinfunction "7_7") (pintype "passive"))
      (node (ref "S6") (pin "8") (pinfunction "8_8") (pintype "passive"))
      (node (ref "S7") (pin "1") (pinfunction "1_1") (pintype "passive"))
      (node (ref "S7") (pin "2") (pinfunction "2_2") (pintype "passive"))
      (node (ref "S7") (pin "3") (pinfunction "3_3") (pintype "passive"))
      (node (ref "S7") (pin "4") (pinfunction "4_4") (pintype "passive"))
      (node (ref "S7") (pin "5") (pinfunction "5_5") (pintype "passive"))
      (node (ref "S7") (pin "6") (pinfunction "6_6") (pintype "passive"))
      (node (ref "S7") (pin "7") (pinfunction "7_7") (pintype "passive"))
      (node (ref "S7") (pin "8") (pinfunction "8_8") (pintype "passive"))
      (node (ref "S8") (pin "1") (pinfunction "1_1") (pintype "passive"))
      (node (ref "S8") (pin "2") (pinfunction "2_2") (pintype "passive"))
      (node (ref "S8") (pin "3") (pinfunction "3_3") (pintype "passive"))
      (node (ref "S8") (pin "4") (pinfunction "4_4") (pintype "passive"))
      (node (ref "S8") (pin "5") (pinfunction "5_5") (pintype "passive"))
      (node (ref "S8") (pin "6") (pinfunction "6_6") (pintype "passive"))
      (node (ref "S8") (pin "7") (pinfunction "7_7") (pintype "passive"))
      (node (ref "S8") (pin "8") (pinfunction "8_8") (pintype "passive"))
      (node (ref "S9") (pin "1") (pinfunction "1_1") (pintype "passive"))
      (node (ref "S9") (pin "2") (pinfunction "2_2") (pintype "passive"))
      (node (ref "S9") (pin "3") (pinfunction "3_3") (pintype "passive"))
      (node (ref "S9") (pin "4") (pinfunction "4_4") (pintype "passive"))
      (node (ref "S9") (pin "5") (pinfunction "5_5") (pintype "passive"))
      (node (ref "S9") (pin "6") (pinfunction "6_6") (pintype "passive"))
      (node (ref "S9") (pin "7") (pinfunction "7_7") (pintype "passive"))
      (node (ref "S9") (pin "8") (pinfunction "8_8") (pintype "passive"))
      (node (ref "SIG_IN") (pin "P$GND") (pinfunction "GND_P$GND") (pintype "bidirectional"))
      (node (ref "TP1") (pin "TP") (pinfunction "TP_TP") (pintype "input"))
      (node (ref "TP10") (pin "P$1") (pinfunction "TP_P$1") (pintype "input"))
      (node (ref "TP11") (pin "P$1") (pinfunction "TP_P$1") (pintype "input"))
      (node (ref "TP12") (pin "P$1") (pinfunction "TP_P$1") (pintype "input"))
      (node (ref "TP13") (pin "P$1") (pinfunction "TP_P$1") (pintype "input"))
      (node (ref "TP2") (pin "TP") (pinfunction "TP_TP") (pintype "input"))
      (node (ref "TP3") (pin "TP") (pinfunction "TP_TP") (pintype "input"))
      (node (ref "TP4") (pin "TP") (pinfunction "TP_TP") (pintype "input"))
      (node (ref "TP5") (pin "TP") (pinfunction "TP_TP") (pintype "input"))
      (node (ref "TP6") (pin "TP") (pinfunction "TP_TP") (pintype "input"))
      (node (ref "U$1") (pin "9") (pinfunction "9_9") (pintype "passive"))
      (node (ref "U$10") (pin "9") (pinfunction "9_9") (pintype "passive"))
      (node (ref "U$11") (pin "9") (pinfunction "9_9") (pintype "passive"))
      (node (ref "U$12") (pin "9") (pinfunction "9_9") (pintype "passive"))
      (node (ref "U$13") (pin "9") (pinfunction "9_9") (pintype "passive"))
      (node (ref "U$14") (pin "9") (pinfunction "9_9") (pintype "passive"))
      (node (ref "U$15") (pin "9") (pinfunction "9_9") (pintype "passive"))
      (node (ref "U$16") (pin "9") (pinfunction "9_9") (pintype "passive"))
      (node (ref "U$2") (pin "9") (pinfunction "9_9") (pintype "passive"))
      (node (ref "U$3") (pin "9") (pinfunction "9_9") (pintype "passive"))
      (node (ref "U$4") (pin "9") (pinfunction "9_9") (pintype "passive"))
      (node (ref "U$5") (pin "9") (pinfunction "9_9") (pintype "passive"))
      (node (ref "U$6") (pin "9") (pinfunction "9_9") (pintype "passive"))
      (node (ref "U$7") (pin "9") (pinfunction "9_9") (pintype "passive"))
      (node (ref "U$8") (pin "9") (pinfunction "9_9") (pintype "passive"))
      (node (ref "U$9") (pin "9") (pinfunction "9_9") (pintype "passive"))
    )
    (net (code "17") (name "Net-(AIN_N0T-Pad2)") (class "Default")
      (node (ref "AIN_N0T") (pin "2") (pinfunction "2_2") (pintype "bidirectional"))
      (node (ref "R4") (pin "1") (pinfunction "1_1") (pintype "passive"))
      (node (ref "S4") (pin "16") (pinfunction "16_16") (pintype "passive"))
      (node (ref "U$4") (pin "1") (pinfunction "1_1") (pintype "passive"))
    )
    (net (code "18") (name "Net-(AIN_N0T-Pad3)") (class "Default")
      (node (ref "AIN_N0T") (pin "3") (pinfunction "3_3") (pintype "bidirectional"))
      (node (ref "R4") (pin "2") (pinfunction "2_2") (pintype "passive"))
      (node (ref "S4") (pin "15") (pinfunction "15_15") (pintype "passive"))
      (node (ref "U$4") (pin "2") (pinfunction "2_2") (pintype "passive"))
    )
    (net (code "19") (name "Net-(AIN_N0T-Pad4)") (class "Default")
      (node (ref "AIN_N0T") (pin "4") (pinfunction "4_4") (pintype "bidirectional"))
      (node (ref "R4") (pin "3") (pinfunction "3_3") (pintype "passive"))
      (node (ref "S4") (pin "14") (pinfunction "14_14") (pintype "passive"))
      (node (ref "U$4") (pin "3") (pinfunction "3_3") (pintype "passive"))
    )
    (net (code "20") (name "Net-(AIN_N0T-Pad5)") (class "Default")
      (node (ref "AIN_N0T") (pin "5") (pinfunction "5_5") (pintype "bidirectional"))
      (node (ref "R4") (pin "4") (pinfunction "4_4") (pintype "passive"))
      (node (ref "S4") (pin "13") (pinfunction "13_13") (pintype "passive"))
      (node (ref "U$4") (pin "4") (pinfunction "4_4") (pintype "passive"))
    )
    (net (code "21") (name "Net-(AIN_N0T-Pad6)") (class "Default")
      (node (ref "AIN_N0T") (pin "6") (pinfunction "6_6") (pintype "bidirectional"))
      (node (ref "R4") (pin "5") (pinfunction "5_5") (pintype "passive"))
      (node (ref "S4") (pin "12") (pinfunction "12_12") (pintype "passive"))
      (node (ref "U$4") (pin "5") (pinfunction "5_5") (pintype "passive"))
    )
    (net (code "22") (name "Net-(AIN_N0T-Pad7)") (class "Default")
      (node (ref "AIN_N0T") (pin "7") (pinfunction "7_7") (pintype "bidirectional"))
      (node (ref "R4") (pin "6") (pinfunction "6_6") (pintype "passive"))
      (node (ref "S4") (pin "11") (pinfunction "11_11") (pintype "passive"))
      (node (ref "U$4") (pin "6") (pinfunction "6_6") (pintype "passive"))
    )
    (net (code "23") (name "Net-(AIN_N0T-Pad8)") (class "Default")
      (node (ref "AIN_N0T") (pin "8") (pinfunction "8_8") (pintype "bidirectional"))
      (node (ref "R4") (pin "7") (pinfunction "7_7") (pintype "passive"))
      (node (ref "S4") (pin "10") (pinfunction "10_10") (pintype "passive"))
      (node (ref "U$4") (pin "7") (pinfunction "7_7") (pintype "passive"))
    )
    (net (code "24") (name "Net-(AIN_N0T-Pad9)") (class "Default")
      (node (ref "AIN_N0T") (pin "9") (pinfunction "9_9") (pintype "bidirectional"))
      (node (ref "R4") (pin "8") (pinfunction "8_8") (pintype "passive"))
      (node (ref "S4") (pin "9") (pinfunction "9_9") (pintype "passive"))
      (node (ref "U$4") (pin "8") (pinfunction "8_8") (pintype "passive"))
    )
    (net (code "25") (name "Net-(AIN_N0T-Pad10)") (class "Default")
      (node (ref "AIN_N0T") (pin "10") (pinfunction "10_10") (pintype "bidirectional"))
      (node (ref "R3") (pin "1") (pinfunction "1_1") (pintype "passive"))
      (node (ref "S3") (pin "16") (pinfunction "16_16") (pintype "passive"))
      (node (ref "U$3") (pin "1") (pinfunction "1_1") (pintype "passive"))
    )
    (net (code "26") (name "Net-(AIN_N0T-Pad11)") (class "Default")
      (node (ref "AIN_N0T") (pin "11") (pinfunction "11_11") (pintype "bidirectional"))
      (node (ref "R3") (pin "2") (pinfunction "2_2") (pintype "passive"))
      (node (ref "S3") (pin "15") (pinfunction "15_15") (pintype "passive"))
      (node (ref "U$3") (pin "2") (pinfunction "2_2") (pintype "passive"))
    )
    (net (code "27") (name "Net-(AIN_N0T-Pad12)") (class "Default")
      (node (ref "AIN_N0T") (pin "12") (pinfunction "12_12") (pintype "bidirectional"))
      (node (ref "R3") (pin "3") (pinfunction "3_3") (pintype "passive"))
      (node (ref "S3") (pin "14") (pinfunction "14_14") (pintype "passive"))
      (node (ref "U$3") (pin "3") (pinfunction "3_3") (pintype "passive"))
    )
    (net (code "28") (name "Net-(AIN_N0T-Pad13)") (class "Default")
      (node (ref "AIN_N0T") (pin "13") (pinfunction "13_13") (pintype "bidirectional"))
      (node (ref "R3") (pin "4") (pinfunction "4_4") (pintype "passive"))
      (node (ref "S3") (pin "13") (pinfunction "13_13") (pintype "passive"))
      (node (ref "U$3") (pin "4") (pinfunction "4_4") (pintype "passive"))
    )
    (net (code "29") (name "Net-(AIN_N0T-Pad14)") (class "Default")
      (node (ref "AIN_N0T") (pin "14") (pinfunction "14_14") (pintype "bidirectional"))
      (node (ref "R3") (pin "5") (pinfunction "5_5") (pintype "passive"))
      (node (ref "S3") (pin "12") (pinfunction "12_12") (pintype "passive"))
      (node (ref "U$3") (pin "5") (pinfunction "5_5") (pintype "passive"))
    )
    (net (code "30") (name "Net-(AIN_N0T-Pad15)") (class "Default")
      (node (ref "AIN_N0T") (pin "15") (pinfunction "15_15") (pintype "bidirectional"))
      (node (ref "R3") (pin "6") (pinfunction "6_6") (pintype "passive"))
      (node (ref "S3") (pin "11") (pinfunction "11_11") (pintype "passive"))
      (node (ref "U$3") (pin "6") (pinfunction "6_6") (pintype "passive"))
    )
    (net (code "31") (name "Net-(AIN_N0T-Pad16)") (class "Default")
      (node (ref "AIN_N0T") (pin "16") (pinfunction "16_16") (pintype "bidirectional"))
      (node (ref "R3") (pin "7") (pinfunction "7_7") (pintype "passive"))
      (node (ref "S3") (pin "10") (pinfunction "10_10") (pintype "passive"))
      (node (ref "U$3") (pin "7") (pinfunction "7_7") (pintype "passive"))
    )
    (net (code "32") (name "Net-(AIN_N0T-Pad17)") (class "Default")
      (node (ref "AIN_N0T") (pin "17") (pinfunction "17_17") (pintype "bidirectional"))
      (node (ref "R3") (pin "8") (pinfunction "8_8") (pintype "passive"))
      (node (ref "S3") (pin "9") (pinfunction "9_9") (pintype "passive"))
      (node (ref "U$3") (pin "8") (pinfunction "8_8") (pintype "passive"))
    )
    (net (code "33") (name "Net-(AIN_N0T-Pad18)") (class "Default")
      (node (ref "AIN_N0T") (pin "18") (pinfunction "18_18") (pintype "bidirectional"))
      (node (ref "R2") (pin "1") (pinfunction "1_1") (pintype "passive"))
      (node (ref "S2") (pin "16") (pinfunction "16_16") (pintype "passive"))
      (node (ref "U$2") (pin "1") (pinfunction "1_1") (pintype "passive"))
    )
    (net (code "34") (name "Net-(AIN_N0T-Pad19)") (class "Default")
      (node (ref "AIN_N0T") (pin "19") (pinfunction "19_19") (pintype "bidirectional"))
      (node (ref "R2") (pin "2") (pinfunction "2_2") (pintype "passive"))
      (node (ref "S2") (pin "15") (pinfunction "15_15") (pintype "passive"))
      (node (ref "U$2") (pin "2") (pinfunction "2_2") (pintype "passive"))
    )
    (net (code "35") (name "Net-(AIN_N0T-Pad20)") (class "Default")
      (node (ref "AIN_N0T") (pin "20") (pinfunction "20_20") (pintype "bidirectional"))
      (node (ref "R2") (pin "3") (pinfunction "3_3") (pintype "passive"))
      (node (ref "S2") (pin "14") (pinfunction "14_14") (pintype "passive"))
      (node (ref "U$2") (pin "3") (pinfunction "3_3") (pintype "passive"))
    )
    (net (code "36") (name "Net-(AIN_N0T-Pad21)") (class "Default")
      (node (ref "AIN_N0T") (pin "21") (pinfunction "21_21") (pintype "bidirectional"))
      (node (ref "R2") (pin "4") (pinfunction "4_4") (pintype "passive"))
      (node (ref "S2") (pin "13") (pinfunction "13_13") (pintype "passive"))
      (node (ref "U$2") (pin "4") (pinfunction "4_4") (pintype "passive"))
    )
    (net (code "37") (name "Net-(AIN_N0T-Pad22)") (class "Default")
      (node (ref "AIN_N0T") (pin "22") (pinfunction "22_22") (pintype "bidirectional"))
      (node (ref "R2") (pin "5") (pinfunction "5_5") (pintype "passive"))
      (node (ref "S2") (pin "12") (pinfunction "12_12") (pintype "passive"))
      (node (ref "U$2") (pin "5") (pinfunction "5_5") (pintype "passive"))
    )
    (net (code "38") (name "Net-(AIN_N0T-Pad23)") (class "Default")
      (node (ref "AIN_N0T") (pin "23") (pinfunction "23_23") (pintype "bidirectional"))
      (node (ref "R2") (pin "6") (pinfunction "6_6") (pintype "passive"))
      (node (ref "S2") (pin "11") (pinfunction "11_11") (pintype "passive"))
      (node (ref "U$2") (pin "6") (pinfunction "6_6") (pintype "passive"))
    )
    (net (code "39") (name "Net-(AIN_N0T-Pad24)") (class "Default")
      (node (ref "AIN_N0T") (pin "24") (pinfunction "24_24") (pintype "bidirectional"))
      (node (ref "R2") (pin "7") (pinfunction "7_7") (pintype "passive"))
      (node (ref "S2") (pin "10") (pinfunction "10_10") (pintype "passive"))
      (node (ref "U$2") (pin "7") (pinfunction "7_7") (pintype "passive"))
    )
    (net (code "40") (name "Net-(AIN_N0T-Pad25)") (class "Default")
      (node (ref "AIN_N0T") (pin "25") (pinfunction "25_25") (pintype "bidirectional"))
      (node (ref "R2") (pin "8") (pinfunction "8_8") (pintype "passive"))
      (node (ref "S2") (pin "9") (pinfunction "9_9") (pintype "passive"))
      (node (ref "U$2") (pin "8") (pinfunction "8_8") (pintype "passive"))
    )
    (net (code "41") (name "Net-(AIN_N0T-Pad26)") (class "Default")
      (node (ref "AIN_N0T") (pin "26") (pinfunction "26_26") (pintype "bidirectional"))
      (node (ref "R1") (pin "1") (pinfunction "1_1") (pintype "passive"))
      (node (ref "S1") (pin "16") (pinfunction "16_16") (pintype "passive"))
      (node (ref "U$1") (pin "1") (pinfunction "1_1") (pintype "passive"))
    )
    (net (code "42") (name "Net-(AIN_N0T-Pad27)") (class "Default")
      (node (ref "AIN_N0T") (pin "27") (pinfunction "27_27") (pintype "bidirectional"))
      (node (ref "R1") (pin "2") (pinfunction "2_2") (pintype "passive"))
      (node (ref "S1") (pin "15") (pinfunction "15_15") (pintype "passive"))
      (node (ref "U$1") (pin "2") (pinfunction "2_2") (pintype "passive"))
    )
    (net (code "43") (name "Net-(AIN_N0T-Pad28)") (class "Default")
      (node (ref "AIN_N0T") (pin "28") (pinfunction "28_28") (pintype "bidirectional"))
      (node (ref "R1") (pin "3") (pinfunction "3_3") (pintype "passive"))
      (node (ref "S1") (pin "14") (pinfunction "14_14") (pintype "passive"))
      (node (ref "U$1") (pin "3") (pinfunction "3_3") (pintype "passive"))
    )
    (net (code "44") (name "Net-(AIN_N0T-Pad29)") (class "Default")
      (node (ref "AIN_N0T") (pin "29") (pinfunction "29_29") (pintype "bidirectional"))
      (node (ref "R1") (pin "4") (pinfunction "4_4") (pintype "passive"))
      (node (ref "S1") (pin "13") (pinfunction "13_13") (pintype "passive"))
      (node (ref "U$1") (pin "4") (pinfunction "4_4") (pintype "passive"))
    )
    (net (code "45") (name "Net-(AIN_N0T-Pad30)") (class "Default")
      (node (ref "AIN_N0T") (pin "30") (pinfunction "30_30") (pintype "bidirectional"))
      (node (ref "R1") (pin "5") (pinfunction "5_5") (pintype "passive"))
      (node (ref "S1") (pin "12") (pinfunction "12_12") (pintype "passive"))
      (node (ref "U$1") (pin "5") (pinfunction "5_5") (pintype "passive"))
    )
    (net (code "46") (name "Net-(AIN_N0T-Pad31)") (class "Default")
      (node (ref "AIN_N0T") (pin "31") (pinfunction "31_31") (pintype "bidirectional"))
      (node (ref "R1") (pin "6") (pinfunction "6_6") (pintype "passive"))
      (node (ref "S1") (pin "11") (pinfunction "11_11") (pintype "passive"))
      (node (ref "U$1") (pin "6") (pinfunction "6_6") (pintype "passive"))
    )
    (net (code "47") (name "Net-(AIN_N0T-Pad32)") (class "Default")
      (node (ref "AIN_N0T") (pin "32") (pinfunction "32_32") (pintype "bidirectional"))
      (node (ref "R1") (pin "7") (pinfunction "7_7") (pintype "passive"))
      (node (ref "S1") (pin "10") (pinfunction "10_10") (pintype "passive"))
      (node (ref "U$1") (pin "7") (pinfunction "7_7") (pintype "passive"))
    )
    (net (code "48") (name "Net-(AIN_N0T-Pad33)") (class "Default")
      (node (ref "AIN_N0T") (pin "33") (pinfunction "33_33") (pintype "bidirectional"))
      (node (ref "R1") (pin "8") (pinfunction "8_8") (pintype "passive"))
      (node (ref "S1") (pin "9") (pinfunction "9_9") (pintype "passive"))
      (node (ref "U$1") (pin "8") (pinfunction "8_8") (pintype "passive"))
    )
    (net (code "49") (name "Net-(AIN_N0T-Pad37)") (class "Default")
      (node (ref "AIN_N0T") (pin "37") (pinfunction "37_37") (pintype "bidirectional"))
      (node (ref "R5") (pin "1") (pinfunction "1_1") (pintype "passive"))
      (node (ref "S5") (pin "16") (pinfunction "16_16") (pintype "passive"))
      (node (ref "U$5") (pin "1") (pinfunction "1_1") (pintype "passive"))
    )
    (net (code "50") (name "Net-(AIN_N0T-Pad38)") (class "Default")
      (node (ref "AIN_N0T") (pin "38") (pinfunction "38_38") (pintype "bidirectional"))
      (node (ref "R5") (pin "2") (pinfunction "2_2") (pintype "passive"))
      (node (ref "S5") (pin "15") (pinfunction "15_15") (pintype "passive"))
      (node (ref "U$5") (pin "2") (pinfunction "2_2") (pintype "passive"))
    )
    (net (code "51") (name "Net-(AIN_N0T-Pad39)") (class "Default")
      (node (ref "AIN_N0T") (pin "39") (pinfunction "39_39") (pintype "bidirectional"))
      (node (ref "R5") (pin "3") (pinfunction "3_3") (pintype "passive"))
      (node (ref "S5") (pin "14") (pinfunction "14_14") (pintype "passive"))
      (node (ref "U$5") (pin "3") (pinfunction "3_3") (pintype "passive"))
    )
    (net (code "52") (name "Net-(AIN_N0T-Pad40)") (class "Default")
      (node (ref "AIN_N0T") (pin "40") (pinfunction "40_40") (pintype "bidirectional"))
      (node (ref "R5") (pin "4") (pinfunction "4_4") (pintype "passive"))
      (node (ref "S5") (pin "13") (pinfunction "13_13") (pintype "passive"))
      (node (ref "U$5") (pin "4") (pinfunction "4_4") (pintype "passive"))
    )
    (net (code "53") (name "Net-(AIN_N0T-Pad41)") (class "Default")
      (node (ref "AIN_N0T") (pin "41") (pinfunction "41_41") (pintype "bidirectional"))
      (node (ref "R5") (pin "5") (pinfunction "5_5") (pintype "passive"))
      (node (ref "S5") (pin "12") (pinfunction "12_12") (pintype "passive"))
      (node (ref "U$5") (pin "5") (pinfunction "5_5") (pintype "passive"))
    )
    (net (code "54") (name "Net-(AIN_N0T-Pad42)") (class "Default")
      (node (ref "AIN_N0T") (pin "42") (pinfunction "42_42") (pintype "bidirectional"))
      (node (ref "R5") (pin "6") (pinfunction "6_6") (pintype "passive"))
      (node (ref "S5") (pin "11") (pinfunction "11_11") (pintype "passive"))
      (node (ref "U$5") (pin "6") (pinfunction "6_6") (pintype "passive"))
    )
    (net (code "55") (name "Net-(AIN_N0T-Pad43)") (class "Default")
      (node (ref "AIN_N0T") (pin "43") (pinfunction "43_43") (pintype "bidirectional"))
      (node (ref "R5") (pin "7") (pinfunction "7_7") (pintype "passive"))
      (node (ref "S5") (pin "10") (pinfunction "10_10") (pintype "passive"))
      (node (ref "U$5") (pin "7") (pinfunction "7_7") (pintype "passive"))
    )
    (net (code "56") (name "Net-(AIN_N0T-Pad44)") (class "Default")
      (node (ref "AIN_N0T") (pin "44") (pinfunction "44_44") (pintype "bidirectional"))
      (node (ref "R5") (pin "8") (pinfunction "8_8") (pintype "passive"))
      (node (ref "S5") (pin "9") (pinfunction "9_9") (pintype "passive"))
      (node (ref "U$5") (pin "8") (pinfunction "8_8") (pintype "passive"))
    )
    (net (code "57") (name "Net-(AIN_N0T-Pad45)") (class "Default")
      (node (ref "AIN_N0T") (pin "45") (pinfunction "45_45") (pintype "bidirectional"))
      (node (ref "R6") (pin "1") (pinfunction "1_1") (pintype "passive"))
      (node (ref "S6") (pin "16") (pinfunction "16_16") (pintype "passive"))
      (node (ref "U$6") (pin "1") (pinfunction "1_1") (pintype "passive"))
    )
    (net (code "58") (name "Net-(AIN_N0T-Pad46)") (class "Default")
      (node (ref "AIN_N0T") (pin "46") (pinfunction "46_46") (pintype "bidirectional"))
      (node (ref "R6") (pin "2") (pinfunction "2_2") (pintype "passive"))
      (node (ref "S6") (pin "15") (pinfunction "15_15") (pintype "passive"))
      (node (ref "U$6") (pin "2") (pinfunction "2_2") (pintype "passive"))
    )
    (net (code "59") (name "Net-(AIN_N0T-Pad47)") (class "Default")
      (node (ref "AIN_N0T") (pin "47") (pinfunction "47_47") (pintype "bidirectional"))
      (node (ref "R6") (pin "3") (pinfunction "3_3") (pintype "passive"))
      (node (ref "S6") (pin "14") (pinfunction "14_14") (pintype "passive"))
      (node (ref "U$6") (pin "3") (pinfunction "3_3") (pintype "passive"))
    )
    (net (code "60") (name "Net-(AIN_N0T-Pad48)") (class "Default")
      (node (ref "AIN_N0T") (pin "48") (pinfunction "48_48") (pintype "bidirectional"))
      (node (ref "R6") (pin "4") (pinfunction "4_4") (pintype "passive"))
      (node (ref "S6") (pin "13") (pinfunction "13_13") (pintype "passive"))
      (node (ref "U$6") (pin "4") (pinfunction "4_4") (pintype "passive"))
    )
    (net (code "61") (name "Net-(AIN_N0T-Pad49)") (class "Default")
      (node (ref "AIN_N0T") (pin "49") (pinfunction "49_49") (pintype "bidirectional"))
      (node (ref "R6") (pin "5") (pinfunction "5_5") (pintype "passive"))
      (node (ref "S6") (pin "12") (pinfunction "12_12") (pintype "passive"))
      (node (ref "U$6") (pin "5") (pinfunction "5_5") (pintype "passive"))
    )
    (net (code "62") (name "Net-(AIN_N0T-Pad50)") (class "Default")
      (node (ref "AIN_N0T") (pin "50") (pinfunction "50_50") (pintype "bidirectional"))
      (node (ref "R6") (pin "6") (pinfunction "6_6") (pintype "passive"))
      (node (ref "S6") (pin "11") (pinfunction "11_11") (pintype "passive"))
      (node (ref "U$6") (pin "6") (pinfunction "6_6") (pintype "passive"))
    )
    (net (code "63") (name "Net-(AIN_N0T-Pad51)") (class "Default")
      (node (ref "AIN_N0T") (pin "51") (pinfunction "51_51") (pintype "bidirectional"))
      (node (ref "R6") (pin "7") (pinfunction "7_7") (pintype "passive"))
      (node (ref "S6") (pin "10") (pinfunction "10_10") (pintype "passive"))
      (node (ref "U$6") (pin "7") (pinfunction "7_7") (pintype "passive"))
    )
    (net (code "64") (name "Net-(AIN_N0T-Pad52)") (class "Default")
      (node (ref "AIN_N0T") (pin "52") (pinfunction "52_52") (pintype "bidirectional"))
      (node (ref "R6") (pin "8") (pinfunction "8_8") (pintype "passive"))
      (node (ref "S6") (pin "9") (pinfunction "9_9") (pintype "passive"))
      (node (ref "U$6") (pin "8") (pinfunction "8_8") (pintype "passive"))
    )
    (net (code "65") (name "Net-(AIN_N0T-Pad53)") (class "Default")
      (node (ref "AIN_N0T") (pin "53") (pinfunction "53_53") (pintype "bidirectional"))
      (node (ref "R7") (pin "1") (pinfunction "1_1") (pintype "passive"))
      (node (ref "S7") (pin "16") (pinfunction "16_16") (pintype "passive"))
      (node (ref "U$7") (pin "1") (pinfunction "1_1") (pintype "passive"))
    )
    (net (code "66") (name "Net-(AIN_N0T-Pad54)") (class "Default")
      (node (ref "AIN_N0T") (pin "54") (pinfunction "54_54") (pintype "bidirectional"))
      (node (ref "R7") (pin "2") (pinfunction "2_2") (pintype "passive"))
      (node (ref "S7") (pin "15") (pinfunction "15_15") (pintype "passive"))
      (node (ref "U$7") (pin "2") (pinfunction "2_2") (pintype "passive"))
    )
    (net (code "67") (name "Net-(AIN_N0T-Pad55)") (class "Default")
      (node (ref "AIN_N0T") (pin "55") (pinfunction "55_55") (pintype "bidirectional"))
      (node (ref "R7") (pin "3") (pinfunction "3_3") (pintype "passive"))
      (node (ref "S7") (pin "14") (pinfunction "14_14") (pintype "passive"))
      (node (ref "U$7") (pin "3") (pinfunction "3_3") (pintype "passive"))
    )
    (net (code "68") (name "Net-(AIN_N0T-Pad56)") (class "Default")
      (node (ref "AIN_N0T") (pin "56") (pinfunction "56_56") (pintype "bidirectional"))
      (node (ref "R7") (pin "4") (pinfunction "4_4") (pintype "passive"))
      (node (ref "S7") (pin "13") (pinfunction "13_13") (pintype "passive"))
      (node (ref "U$7") (pin "4") (pinfunction "4_4") (pintype "passive"))
    )
    (net (code "69") (name "Net-(AIN_N0T-Pad57)") (class "Default")
      (node (ref "AIN_N0T") (pin "57") (pinfunction "57_57") (pintype "bidirectional"))
      (node (ref "R7") (pin "5") (pinfunction "5_5") (pintype "passive"))
      (node (ref "S7") (pin "12") (pinfunction "12_12") (pintype "passive"))
      (node (ref "U$7") (pin "5") (pinfunction "5_5") (pintype "passive"))
    )
    (net (code "70") (name "Net-(AIN_N0T-Pad58)") (class "Default")
      (node (ref "AIN_N0T") (pin "58") (pinfunction "58_58") (pintype "bidirectional"))
      (node (ref "R7") (pin "6") (pinfunction "6_6") (pintype "passive"))
      (node (ref "S7") (pin "11") (pinfunction "11_11") (pintype "passive"))
      (node (ref "U$7") (pin "6") (pinfunction "6_6") (pintype "passive"))
    )
    (net (code "71") (name "Net-(AIN_N0T-Pad59)") (class "Default")
      (node (ref "AIN_N0T") (pin "59") (pinfunction "59_59") (pintype "bidirectional"))
      (node (ref "R7") (pin "7") (pinfunction "7_7") (pintype "passive"))
      (node (ref "S7") (pin "10") (pinfunction "10_10") (pintype "passive"))
      (node (ref "U$7") (pin "7") (pinfunction "7_7") (pintype "passive"))
    )
    (net (code "72") (name "Net-(AIN_N0T-Pad60)") (class "Default")
      (node (ref "AIN_N0T") (pin "60") (pinfunction "60_60") (pintype "bidirectional"))
      (node (ref "R7") (pin "8") (pinfunction "8_8") (pintype "passive"))
      (node (ref "S7") (pin "9") (pinfunction "9_9") (pintype "passive"))
      (node (ref "U$7") (pin "8") (pinfunction "8_8") (pintype "passive"))
    )
    (net (code "73") (name "Net-(AIN_N0T-Pad61)") (class "Default")
      (node (ref "AIN_N0T") (pin "61") (pinfunction "61_61") (pintype "bidirectional"))
      (node (ref "R8") (pin "1") (pinfunction "1_1") (pintype "passive"))
      (node (ref "S8") (pin "16") (pinfunction "16_16") (pintype "passive"))
      (node (ref "U$8") (pin "1") (pinfunction "1_1") (pintype "passive"))
    )
    (net (code "74") (name "Net-(AIN_N0T-Pad62)") (class "Default")
      (node (ref "AIN_N0T") (pin "62") (pinfunction "62_62") (pintype "bidirectional"))
      (node (ref "R8") (pin "2") (pinfunction "2_2") (pintype "passive"))
      (node (ref "S8") (pin "15") (pinfunction "15_15") (pintype "passive"))
      (node (ref "U$8") (pin "2") (pinfunction "2_2") (pintype "passive"))
    )
    (net (code "75") (name "Net-(AIN_N0T-Pad63)") (class "Default")
      (node (ref "AIN_N0T") (pin "63") (pinfunction "63_63") (pintype "bidirectional"))
      (node (ref "R8") (pin "3") (pinfunction "3_3") (pintype "passive"))
      (node (ref "S8") (pin "14") (pinfunction "14_14") (pintype "passive"))
      (node (ref "U$8") (pin "3") (pinfunction "3_3") (pintype "passive"))
    )
    (net (code "76") (name "Net-(AIN_N0T-Pad64)") (class "Default")
      (node (ref "AIN_N0T") (pin "64") (pinfunction "64_64") (pintype "bidirectional"))
      (node (ref "R8") (pin "4") (pinfunction "4_4") (pintype "passive"))
      (node (ref "S8") (pin "13") (pinfunction "13_13") (pintype "passive"))
      (node (ref "U$8") (pin "4") (pinfunction "4_4") (pintype "passive"))
    )
    (net (code "77") (name "Net-(AIN_N0T-Pad65)") (class "Default")
      (node (ref "AIN_N0T") (pin "65") (pinfunction "65_65") (pintype "bidirectional"))
      (node (ref "R8") (pin "5") (pinfunction "5_5") (pintype "passive"))
      (node (ref "S8") (pin "12") (pinfunction "12_12") (pintype "passive"))
      (node (ref "U$8") (pin "5") (pinfunction "5_5") (pintype "passive"))
    )
    (net (code "78") (name "Net-(AIN_N0T-Pad66)") (class "Default")
      (node (ref "AIN_N0T") (pin "66") (pinfunction "66_66") (pintype "bidirectional"))
      (node (ref "R8") (pin "6") (pinfunction "6_6") (pintype "passive"))
      (node (ref "S8") (pin "11") (pinfunction "11_11") (pintype "passive"))
      (node (ref "U$8") (pin "6") (pinfunction "6_6") (pintype "passive"))
    )
    (net (code "79") (name "Net-(AIN_N0T-Pad67)") (class "Default")
      (node (ref "AIN_N0T") (pin "67") (pinfunction "67_67") (pintype "bidirectional"))
      (node (ref "R8") (pin "7") (pinfunction "7_7") (pintype "passive"))
      (node (ref "S8") (pin "10") (pinfunction "10_10") (pintype "passive"))
      (node (ref "U$8") (pin "7") (pinfunction "7_7") (pintype "passive"))
    )
    (net (code "80") (name "Net-(AIN_N0T-Pad68)") (class "Default")
      (node (ref "AIN_N0T") (pin "68") (pinfunction "68_68") (pintype "bidirectional"))
      (node (ref "R8") (pin "8") (pinfunction "8_8") (pintype "passive"))
      (node (ref "S8") (pin "9") (pinfunction "9_9") (pintype "passive"))
      (node (ref "U$8") (pin "8") (pinfunction "8_8") (pintype "passive"))
    )
    (net (code "81") (name "Net-(AIN_S0T-Pad2)") (class "Default")
      (node (ref "AIN_S0T") (pin "2") (pinfunction "2_2") (pintype "bidirectional"))
      (node (ref "R13") (pin "1") (pinfunction "1_1") (pintype "passive"))
      (node (ref "S13") (pin "16") (pinfunction "16_16") (pintype "passive"))
      (node (ref "U$13") (pin "1") (pinfunction "1_1") (pintype "passive"))
    )
    (net (code "82") (name "Net-(AIN_S0T-Pad3)") (class "Default")
      (node (ref "AIN_S0T") (pin "3") (pinfunction "3_3") (pintype "bidirectional"))
      (node (ref "R13") (pin "2") (pinfunction "2_2") (pintype "passive"))
      (node (ref "S13") (pin "15") (pinfunction "15_15") (pintype "passive"))
      (node (ref "U$13") (pin "2") (pinfunction "2_2") (pintype "passive"))
    )
    (net (code "83") (name "Net-(AIN_S0T-Pad4)") (class "Default")
      (node (ref "AIN_S0T") (pin "4") (pinfunction "4_4") (pintype "bidirectional"))
      (node (ref "R13") (pin "3") (pinfunction "3_3") (pintype "passive"))
      (node (ref "S13") (pin "14") (pinfunction "14_14") (pintype "passive"))
      (node (ref "U$13") (pin "3") (pinfunction "3_3") (pintype "passive"))
    )
    (net (code "84") (name "Net-(AIN_S0T-Pad5)") (class "Default")
      (node (ref "AIN_S0T") (pin "5") (pinfunction "5_5") (pintype "bidirectional"))
      (node (ref "R13") (pin "4") (pinfunction "4_4") (pintype "passive"))
      (node (ref "S13") (pin "13") (pinfunction "13_13") (pintype "passive"))
      (node (ref "U$13") (pin "4") (pinfunction "4_4") (pintype "passive"))
    )
    (net (code "85") (name "Net-(AIN_S0T-Pad6)") (class "Default")
      (node (ref "AIN_S0T") (pin "6") (pinfunction "6_6") (pintype "bidirectional"))
      (node (ref "R13") (pin "5") (pinfunction "5_5") (pintype "passive"))
      (node (ref "S13") (pin "12") (pinfunction "12_12") (pintype "passive"))
      (node (ref "U$13") (pin "5") (pinfunction "5_5") (pintype "passive"))
    )
    (net (code "86") (name "Net-(AIN_S0T-Pad7)") (class "Default")
      (node (ref "AIN_S0T") (pin "7") (pinfunction "7_7") (pintype "bidirectional"))
      (node (ref "R13") (pin "6") (pinfunction "6_6") (pintype "passive"))
      (node (ref "S13") (pin "11") (pinfunction "11_11") (pintype "passive"))
      (node (ref "U$13") (pin "6") (pinfunction "6_6") (pintype "passive"))
    )
    (net (code "87") (name "Net-(AIN_S0T-Pad8)") (class "Default")
      (node (ref "AIN_S0T") (pin "8") (pinfunction "8_8") (pintype "bidirectional"))
      (node (ref "R13") (pin "7") (pinfunction "7_7") (pintype "passive"))
      (node (ref "S13") (pin "10") (pinfunction "10_10") (pintype "passive"))
      (node (ref "U$13") (pin "7") (pinfunction "7_7") (pintype "passive"))
    )
    (net (code "88") (name "Net-(AIN_S0T-Pad9)") (class "Default")
      (node (ref "AIN_S0T") (pin "9") (pinfunction "9_9") (pintype "bidirectional"))
      (node (ref "R13") (pin "8") (pinfunction "8_8") (pintype "passive"))
      (node (ref "S13") (pin "9") (pinfunction "9_9") (pintype "passive"))
      (node (ref "U$13") (pin "8") (pinfunction "8_8") (pintype "passive"))
    )
    (net (code "89") (name "Net-(AIN_S0T-Pad10)") (class "Default")
      (node (ref "AIN_S0T") (pin "10") (pinfunction "10_10") (pintype "bidirectional"))
      (node (ref "R14") (pin "1") (pinfunction "1_1") (pintype "passive"))
      (node (ref "S14") (pin "16") (pinfunction "16_16") (pintype "passive"))
      (node (ref "U$14") (pin "1") (pinfunction "1_1") (pintype "passive"))
    )
    (net (code "90") (name "Net-(AIN_S0T-Pad11)") (class "Default")
      (node (ref "AIN_S0T") (pin "11") (pinfunction "11_11") (pintype "bidirectional"))
      (node (ref "R14") (pin "2") (pinfunction "2_2") (pintype "passive"))
      (node (ref "S14") (pin "15") (pinfunction "15_15") (pintype "passive"))
      (node (ref "U$14") (pin "2") (pinfunction "2_2") (pintype "passive"))
    )
    (net (code "91") (name "Net-(AIN_S0T-Pad12)") (class "Default")
      (node (ref "AIN_S0T") (pin "12") (pinfunction "12_12") (pintype "bidirectional"))
      (node (ref "R14") (pin "3") (pinfunction "3_3") (pintype "passive"))
      (node (ref "S14") (pin "14") (pinfunction "14_14") (pintype "passive"))
      (node (ref "U$14") (pin "3") (pinfunction "3_3") (pintype "passive"))
    )
    (net (code "92") (name "Net-(AIN_S0T-Pad13)") (class "Default")
      (node (ref "AIN_S0T") (pin "13") (pinfunction "13_13") (pintype "bidirectional"))
      (node (ref "R14") (pin "4") (pinfunction "4_4") (pintype "passive"))
      (node (ref "S14") (pin "13") (pinfunction "13_13") (pintype "passive"))
      (node (ref "U$14") (pin "4") (pinfunction "4_4") (pintype "passive"))
    )
    (net (code "93") (name "Net-(AIN_S0T-Pad14)") (class "Default")
      (node (ref "AIN_S0T") (pin "14") (pinfunction "14_14") (pintype "bidirectional"))
      (node (ref "R14") (pin "5") (pinfunction "5_5") (pintype "passive"))
      (node (ref "S14") (pin "12") (pinfunction "12_12") (pintype "passive"))
      (node (ref "U$14") (pin "5") (pinfunction "5_5") (pintype "passive"))
    )
    (net (code "94") (name "Net-(AIN_S0T-Pad15)") (class "Default")
      (node (ref "AIN_S0T") (pin "15") (pinfunction "15_15") (pintype "bidirectional"))
      (node (ref "R14") (pin "6") (pinfunction "6_6") (pintype "passive"))
      (node (ref "S14") (pin "11") (pinfunction "11_11") (pintype "passive"))
      (node (ref "U$14") (pin "6") (pinfunction "6_6") (pintype "passive"))
    )
    (net (code "95") (name "Net-(AIN_S0T-Pad16)") (class "Default")
      (node (ref "AIN_S0T") (pin "16") (pinfunction "16_16") (pintype "bidirectional"))
      (node (ref "R14") (pin "7") (pinfunction "7_7") (pintype "passive"))
      (node (ref "S14") (pin "10") (pinfunction "10_10") (pintype "passive"))
      (node (ref "U$14") (pin "7") (pinfunction "7_7") (pintype "passive"))
    )
    (net (code "96") (name "Net-(AIN_S0T-Pad17)") (class "Default")
      (node (ref "AIN_S0T") (pin "17") (pinfunction "17_17") (pintype "bidirectional"))
      (node (ref "R14") (pin "8") (pinfunction "8_8") (pintype "passive"))
      (node (ref "S14") (pin "9") (pinfunction "9_9") (pintype "passive"))
      (node (ref "U$14") (pin "8") (pinfunction "8_8") (pintype "passive"))
    )
    (net (code "97") (name "Net-(AIN_S0T-Pad18)") (class "Default")
      (node (ref "AIN_S0T") (pin "18") (pinfunction "18_18") (pintype "bidirectional"))
      (node (ref "R15") (pin "1") (pinfunction "1_1") (pintype "passive"))
      (node (ref "S15") (pin "16") (pinfunction "16_16") (pintype "passive"))
      (node (ref "U$15") (pin "1") (pinfunction "1_1") (pintype "passive"))
    )
    (net (code "98") (name "Net-(AIN_S0T-Pad19)") (class "Default")
      (node (ref "AIN_S0T") (pin "19") (pinfunction "19_19") (pintype "bidirectional"))
      (node (ref "R15") (pin "2") (pinfunction "2_2") (pintype "passive"))
      (node (ref "S15") (pin "15") (pinfunction "15_15") (pintype "passive"))
      (node (ref "U$15") (pin "2") (pinfunction "2_2") (pintype "passive"))
    )
    (net (code "99") (name "Net-(AIN_S0T-Pad20)") (class "Default")
      (node (ref "AIN_S0T") (pin "20") (pinfunction "20_20") (pintype "bidirectional"))
      (node (ref "R15") (pin "3") (pinfunction "3_3") (pintype "passive"))
      (node (ref "S15") (pin "14") (pinfunction "14_14") (pintype "passive"))
      (node (ref "U$15") (pin "3") (pinfunction "3_3") (pintype "passive"))
    )
    (net (code "100") (name "Net-(AIN_S0T-Pad21)") (class "Default")
      (node (ref "AIN_S0T") (pin "21") (pinfunction "21_21") (pintype "bidirectional"))
      (node (ref "R15") (pin "4") (pinfunction "4_4") (pintype "passive"))
      (node (ref "S15") (pin "13") (pinfunction "13_13") (pintype "passive"))
      (node (ref "U$15") (pin "4") (pinfunction "4_4") (pintype "passive"))
    )
    (net (code "101") (name "Net-(AIN_S0T-Pad22)") (class "Default")
      (node (ref "AIN_S0T") (pin "22") (pinfunction "22_22") (pintype "bidirectional"))
      (node (ref "R15") (pin "5") (pinfunction "5_5") (pintype "passive"))
      (node (ref "S15") (pin "12") (pinfunction "12_12") (pintype "passive"))
      (node (ref "U$15") (pin "5") (pinfunction "5_5") (pintype "passive"))
    )
    (net (code "102") (name "Net-(AIN_S0T-Pad23)") (class "Default")
      (node (ref "AIN_S0T") (pin "23") (pinfunction "23_23") (pintype "bidirectional"))
      (node (ref "R15") (pin "6") (pinfunction "6_6") (pintype "passive"))
      (node (ref "S15") (pin "11") (pinfunction "11_11") (pintype "passive"))
      (node (ref "U$15") (pin "6") (pinfunction "6_6") (pintype "passive"))
    )
    (net (code "103") (name "Net-(AIN_S0T-Pad24)") (class "Default")
      (node (ref "AIN_S0T") (pin "24") (pinfunction "24_24") (pintype "bidirectional"))
      (node (ref "R15") (pin "7") (pinfunction "7_7") (pintype "passive"))
      (node (ref "S15") (pin "10") (pinfunction "10_10") (pintype "passive"))
      (node (ref "U$15") (pin "7") (pinfunction "7_7") (pintype "passive"))
    )
    (net (code "104") (name "Net-(AIN_S0T-Pad25)") (class "Default")
      (node (ref "AIN_S0T") (pin "25") (pinfunction "25_25") (pintype "bidirectional"))
      (node (ref "R15") (pin "8") (pinfunction "8_8") (pintype "passive"))
      (node (ref "S15") (pin "9") (pinfunction "9_9") (pintype "passive"))
      (node (ref "U$15") (pin "8") (pinfunction "8_8") (pintype "passive"))
    )
    (net (code "105") (name "Net-(AIN_S0T-Pad26)") (class "Default")
      (node (ref "AIN_S0T") (pin "26") (pinfunction "26_26") (pintype "bidirectional"))
      (node (ref "R16") (pin "1") (pinfunction "1_1") (pintype "passive"))
      (node (ref "S16") (pin "16") (pinfunction "16_16") (pintype "passive"))
      (node (ref "U$16") (pin "1") (pinfunction "1_1") (pintype "passive"))
    )
    (net (code "106") (name "Net-(AIN_S0T-Pad27)") (class "Default")
      (node (ref "AIN_S0T") (pin "27") (pinfunction "27_27") (pintype "bidirectional"))
      (node (ref "R16") (pin "2") (pinfunction "2_2") (pintype "passive"))
      (node (ref "S16") (pin "15") (pinfunction "15_15") (pintype "passive"))
      (node (ref "U$16") (pin "2") (pinfunction "2_2") (pintype "passive"))
    )
    (net (code "107") (name "Net-(AIN_S0T-Pad28)") (class "Default")
      (node (ref "AIN_S0T") (pin "28") (pinfunction "28_28") (pintype "bidirectional"))
      (node (ref "R16") (pin "3") (pinfunction "3_3") (pintype "passive"))
      (node (ref "S16") (pin "14") (pinfunction "14_14") (pintype "passive"))
      (node (ref "U$16") (pin "3") (pinfunction "3_3") (pintype "passive"))
    )
    (net (code "108") (name "Net-(AIN_S0T-Pad29)") (class "Default")
      (node (ref "AIN_S0T") (pin "29") (pinfunction "29_29") (pintype "bidirectional"))
      (node (ref "R16") (pin "4") (pinfunction "4_4") (pintype "passive"))
      (node (ref "S16") (pin "13") (pinfunction "13_13") (pintype "passive"))
      (node (ref "U$16") (pin "4") (pinfunction "4_4") (pintype "passive"))
    )
    (net (code "109") (name "Net-(AIN_S0T-Pad30)") (class "Default")
      (node (ref "AIN_S0T") (pin "30") (pinfunction "30_30") (pintype "bidirectional"))
      (node (ref "R16") (pin "5") (pinfunction "5_5") (pintype "passive"))
      (node (ref "S16") (pin "12") (pinfunction "12_12") (pintype "passive"))
      (node (ref "U$16") (pin "5") (pinfunction "5_5") (pintype "passive"))
    )
    (net (code "110") (name "Net-(AIN_S0T-Pad31)") (class "Default")
      (node (ref "AIN_S0T") (pin "31") (pinfunction "31_31") (pintype "bidirectional"))
      (node (ref "R16") (pin "6") (pinfunction "6_6") (pintype "passive"))
      (node (ref "S16") (pin "11") (pinfunction "11_11") (pintype "passive"))
      (node (ref "U$16") (pin "6") (pinfunction "6_6") (pintype "passive"))
    )
    (net (code "111") (name "Net-(AIN_S0T-Pad32)") (class "Default")
      (node (ref "AIN_S0T") (pin "32") (pinfunction "32_32") (pintype "bidirectional"))
      (node (ref "R16") (pin "7") (pinfunction "7_7") (pintype "passive"))
      (node (ref "S16") (pin "10") (pinfunction "10_10") (pintype "passive"))
      (node (ref "U$16") (pin "7") (pinfunction "7_7") (pintype "passive"))
    )
    (net (code "112") (name "Net-(AIN_S0T-Pad33)") (class "Default")
      (node (ref "AIN_S0T") (pin "33") (pinfunction "33_33") (pintype "bidirectional"))
      (node (ref "R16") (pin "8") (pinfunction "8_8") (pintype "passive"))
      (node (ref "S16") (pin "9") (pinfunction "9_9") (pintype "passive"))
      (node (ref "U$16") (pin "8") (pinfunction "8_8") (pintype "passive"))
    )
    (net (code "113") (name "Net-(AIN_S0T-Pad37)") (class "Default")
      (node (ref "AIN_S0T") (pin "37") (pinfunction "37_37") (pintype "bidirectional"))
      (node (ref "R12") (pin "1") (pinfunction "1_1") (pintype "passive"))
      (node (ref "S12") (pin "16") (pinfunction "16_16") (pintype "passive"))
      (node (ref "U$12") (pin "1") (pinfunction "1_1") (pintype "passive"))
    )
    (net (code "114") (name "Net-(AIN_S0T-Pad38)") (class "Default")
      (node (ref "AIN_S0T") (pin "38") (pinfunction "38_38") (pintype "bidirectional"))
      (node (ref "R12") (pin "2") (pinfunction "2_2") (pintype "passive"))
      (node (ref "S12") (pin "15") (pinfunction "15_15") (pintype "passive"))
      (node (ref "U$12") (pin "2") (pinfunction "2_2") (pintype "passive"))
    )
    (net (code "115") (name "Net-(AIN_S0T-Pad39)") (class "Default")
      (node (ref "AIN_S0T") (pin "39") (pinfunction "39_39") (pintype "bidirectional"))
      (node (ref "R12") (pin "3") (pinfunction "3_3") (pintype "passive"))
      (node (ref "S12") (pin "14") (pinfunction "14_14") (pintype "passive"))
      (node (ref "U$12") (pin "3") (pinfunction "3_3") (pintype "passive"))
    )
    (net (code "116") (name "Net-(AIN_S0T-Pad40)") (class "Default")
      (node (ref "AIN_S0T") (pin "40") (pinfunction "40_40") (pintype "bidirectional"))
      (node (ref "R12") (pin "4") (pinfunction "4_4") (pintype "passive"))
      (node (ref "S12") (pin "13") (pinfunction "13_13") (pintype "passive"))
      (node (ref "U$12") (pin "4") (pinfunction "4_4") (pintype "passive"))
    )
    (net (code "117") (name "Net-(AIN_S0T-Pad41)") (class "Default")
      (node (ref "AIN_S0T") (pin "41") (pinfunction "41_41") (pintype "bidirectional"))
      (node (ref "R12") (pin "5") (pinfunction "5_5") (pintype "passive"))
      (node (ref "S12") (pin "12") (pinfunction "12_12") (pintype "passive"))
      (node (ref "U$12") (pin "5") (pinfunction "5_5") (pintype "passive"))
    )
    (net (code "118") (name "Net-(AIN_S0T-Pad42)") (class "Default")
      (node (ref "AIN_S0T") (pin "42") (pinfunction "42_42") (pintype "bidirectional"))
      (node (ref "R12") (pin "6") (pinfunction "6_6") (pintype "passive"))
      (node (ref "S12") (pin "11") (pinfunction "11_11") (pintype "passive"))
      (node (ref "U$12") (pin "6") (pinfunction "6_6") (pintype "passive"))
    )
    (net (code "119") (name "Net-(AIN_S0T-Pad43)") (class "Default")
      (node (ref "AIN_S0T") (pin "43") (pinfunction "43_43") (pintype "bidirectional"))
      (node (ref "R12") (pin "7") (pinfunction "7_7") (pintype "passive"))
      (node (ref "S12") (pin "10") (pinfunction "10_10") (pintype "passive"))
      (node (ref "U$12") (pin "7") (pinfunction "7_7") (pintype "passive"))
    )
    (net (code "120") (name "Net-(AIN_S0T-Pad44)") (class "Default")
      (node (ref "AIN_S0T") (pin "44") (pinfunction "44_44") (pintype "bidirectional"))
      (node (ref "R12") (pin "8") (pinfunction "8_8") (pintype "passive"))
      (node (ref "S12") (pin "9") (pinfunction "9_9") (pintype "passive"))
      (node (ref "U$12") (pin "8") (pinfunction "8_8") (pintype "passive"))
    )
    (net (code "121") (name "Net-(AIN_S0T-Pad45)") (class "Default")
      (node (ref "AIN_S0T") (pin "45") (pinfunction "45_45") (pintype "bidirectional"))
      (node (ref "R11") (pin "1") (pinfunction "1_1") (pintype "passive"))
      (node (ref "S11") (pin "16") (pinfunction "16_16") (pintype "passive"))
      (node (ref "U$11") (pin "1") (pinfunction "1_1") (pintype "passive"))
    )
    (net (code "122") (name "Net-(AIN_S0T-Pad46)") (class "Default")
      (node (ref "AIN_S0T") (pin "46") (pinfunction "46_46") (pintype "bidirectional"))
      (node (ref "R11") (pin "2") (pinfunction "2_2") (pintype "passive"))
      (node (ref "S11") (pin "15") (pinfunction "15_15") (pintype "passive"))
      (node (ref "U$11") (pin "2") (pinfunction "2_2") (pintype "passive"))
    )
    (net (code "123") (name "Net-(AIN_S0T-Pad47)") (class "Default")
      (node (ref "AIN_S0T") (pin "47") (pinfunction "47_47") (pintype "bidirectional"))
      (node (ref "R11") (pin "3") (pinfunction "3_3") (pintype "passive"))
      (node (ref "S11") (pin "14") (pinfunction "14_14") (pintype "passive"))
      (node (ref "U$11") (pin "3") (pinfunction "3_3") (pintype "passive"))
    )
    (net (code "124") (name "Net-(AIN_S0T-Pad48)") (class "Default")
      (node (ref "AIN_S0T") (pin "48") (pinfunction "48_48") (pintype "bidirectional"))
      (node (ref "R11") (pin "4") (pinfunction "4_4") (pintype "passive"))
      (node (ref "S11") (pin "13") (pinfunction "13_13") (pintype "passive"))
      (node (ref "U$11") (pin "4") (pinfunction "4_4") (pintype "passive"))
    )
    (net (code "125") (name "Net-(AIN_S0T-Pad49)") (class "Default")
      (node (ref "AIN_S0T") (pin "49") (pinfunction "49_49") (pintype "bidirectional"))
      (node (ref "R11") (pin "5") (pinfunction "5_5") (pintype "passive"))
      (node (ref "S11") (pin "12") (pinfunction "12_12") (pintype "passive"))
      (node (ref "U$11") (pin "5") (pinfunction "5_5") (pintype "passive"))
    )
    (net (code "126") (name "Net-(AIN_S0T-Pad50)") (class "Default")
      (node (ref "AIN_S0T") (pin "50") (pinfunction "50_50") (pintype "bidirectional"))
      (node (ref "R11") (pin "6") (pinfunction "6_6") (pintype "passive"))
      (node (ref "S11") (pin "11") (pinfunction "11_11") (pintype "passive"))
      (node (ref "U$11") (pin "6") (pinfunction "6_6") (pintype "passive"))
    )
    (net (code "127") (name "Net-(AIN_S0T-Pad51)") (class "Default")
      (node (ref "AIN_S0T") (pin "51") (pinfunction "51_51") (pintype "bidirectional"))
      (node (ref "R11") (pin "7") (pinfunction "7_7") (pintype "passive"))
      (node (ref "S11") (pin "10") (pinfunction "10_10") (pintype "passive"))
      (node (ref "U$11") (pin "7") (pinfunction "7_7") (pintype "passive"))
    )
    (net (code "128") (name "Net-(AIN_S0T-Pad52)") (class "Default")
      (node (ref "AIN_S0T") (pin "52") (pinfunction "52_52") (pintype "bidirectional"))
      (node (ref "R11") (pin "8") (pinfunction "8_8") (pintype "passive"))
      (node (ref "S11") (pin "9") (pinfunction "9_9") (pintype "passive"))
      (node (ref "U$11") (pin "8") (pinfunction "8_8") (pintype "passive"))
    )
    (net (code "129") (name "Net-(AIN_S0T-Pad53)") (class "Default")
      (node (ref "AIN_S0T") (pin "53") (pinfunction "53_53") (pintype "bidirectional"))
      (node (ref "R10") (pin "1") (pinfunction "1_1") (pintype "passive"))
      (node (ref "S10") (pin "16") (pinfunction "16_16") (pintype "passive"))
      (node (ref "U$10") (pin "1") (pinfunction "1_1") (pintype "passive"))
    )
    (net (code "130") (name "Net-(AIN_S0T-Pad54)") (class "Default")
      (node (ref "AIN_S0T") (pin "54") (pinfunction "54_54") (pintype "bidirectional"))
      (node (ref "R10") (pin "2") (pinfunction "2_2") (pintype "passive"))
      (node (ref "S10") (pin "15") (pinfunction "15_15") (pintype "passive"))
      (node (ref "U$10") (pin "2") (pinfunction "2_2") (pintype "passive"))
    )
    (net (code "131") (name "Net-(AIN_S0T-Pad55)") (class "Default")
      (node (ref "AIN_S0T") (pin "55") (pinfunction "55_55") (pintype "bidirectional"))
      (node (ref "R10") (pin "3") (pinfunction "3_3") (pintype "passive"))
      (node (ref "S10") (pin "14") (pinfunction "14_14") (pintype "passive"))
      (node (ref "U$10") (pin "3") (pinfunction "3_3") (pintype "passive"))
    )
    (net (code "132") (name "Net-(AIN_S0T-Pad56)") (class "Default")
      (node (ref "AIN_S0T") (pin "56") (pinfunction "56_56") (pintype "bidirectional"))
      (node (ref "R10") (pin "4") (pinfunction "4_4") (pintype "passive"))
      (node (ref "S10") (pin "13") (pinfunction "13_13") (pintype "passive"))
      (node (ref "U$10") (pin "4") (pinfunction "4_4") (pintype "passive"))
    )
    (net (code "133") (name "Net-(AIN_S0T-Pad57)") (class "Default")
      (node (ref "AIN_S0T") (pin "57") (pinfunction "57_57") (pintype "bidirectional"))
      (node (ref "R10") (pin "5") (pinfunction "5_5") (pintype "passive"))
      (node (ref "S10") (pin "12") (pinfunction "12_12") (pintype "passive"))
      (node (ref "U$10") (pin "5") (pinfunction "5_5") (pintype "passive"))
    )
    (net (code "134") (name "Net-(AIN_S0T-Pad58)") (class "Default")
      (node (ref "AIN_S0T") (pin "58") (pinfunction "58_58") (pintype "bidirectional"))
      (node (ref "R10") (pin "6") (pinfunction "6_6") (pintype "passive"))
      (node (ref "S10") (pin "11") (pinfunction "11_11") (pintype "passive"))
      (node (ref "U$10") (pin "6") (pinfunction "6_6") (pintype "passive"))
    )
    (net (code "135") (name "Net-(AIN_S0T-Pad59)") (class "Default")
      (node (ref "AIN_S0T") (pin "59") (pinfunction "59_59") (pintype "bidirectional"))
      (node (ref "R10") (pin "7") (pinfunction "7_7") (pintype "passive"))
      (node (ref "S10") (pin "10") (pinfunction "10_10") (pintype "passive"))
      (node (ref "U$10") (pin "7") (pinfunction "7_7") (pintype "passive"))
    )
    (net (code "136") (name "Net-(AIN_S0T-Pad60)") (class "Default")
      (node (ref "AIN_S0T") (pin "60") (pinfunction "60_60") (pintype "bidirectional"))
      (node (ref "R10") (pin "8") (pinfunction "8_8") (pintype "passive"))
      (node (ref "S10") (pin "9") (pinfunction "9_9") (pintype "passive"))
      (node (ref "U$10") (pin "8") (pinfunction "8_8") (pintype "passive"))
    )
    (net (code "137") (name "Net-(AIN_S0T-Pad61)") (class "Default")
      (node (ref "AIN_S0T") (pin "61") (pinfunction "61_61") (pintype "bidirectional"))
      (node (ref "R9") (pin "1") (pinfunction "1_1") (pintype "passive"))
      (node (ref "S9") (pin "16") (pinfunction "16_16") (pintype "passive"))
      (node (ref "U$9") (pin "1") (pinfunction "1_1") (pintype "passive"))
    )
    (net (code "138") (name "Net-(AIN_S0T-Pad62)") (class "Default")
      (node (ref "AIN_S0T") (pin "62") (pinfunction "62_62") (pintype "bidirectional"))
      (node (ref "R9") (pin "2") (pinfunction "2_2") (pintype "passive"))
      (node (ref "S9") (pin "15") (pinfunction "15_15") (pintype "passive"))
      (node (ref "U$9") (pin "2") (pinfunction "2_2") (pintype "passive"))
    )
    (net (code "139") (name "Net-(AIN_S0T-Pad63)") (class "Default")
      (node (ref "AIN_S0T") (pin "63") (pinfunction "63_63") (pintype "bidirectional"))
      (node (ref "R9") (pin "3") (pinfunction "3_3") (pintype "passive"))
      (node (ref "S9") (pin "14") (pinfunction "14_14") (pintype "passive"))
      (node (ref "U$9") (pin "3") (pinfunction "3_3") (pintype "passive"))
    )
    (net (code "140") (name "Net-(AIN_S0T-Pad64)") (class "Default")
      (node (ref "AIN_S0T") (pin "64") (pinfunction "64_64") (pintype "bidirectional"))
      (node (ref "R9") (pin "4") (pinfunction "4_4") (pintype "passive"))
      (node (ref "S9") (pin "13") (pinfunction "13_13") (pintype "passive"))
      (node (ref "U$9") (pin "4") (pinfunction "4_4") (pintype "passive"))
    )
    (net (code "141") (name "Net-(AIN_S0T-Pad65)") (class "Default")
      (node (ref "AIN_S0T") (pin "65") (pinfunction "65_65") (pintype "bidirectional"))
      (node (ref "R9") (pin "5") (pinfunction "5_5") (pintype "passive"))
      (node (ref "S9") (pin "12") (pinfunction "12_12") (pintype "passive"))
      (node (ref "U$9") (pin "5") (pinfunction "5_5") (pintype "passive"))
    )
    (net (code "142") (name "Net-(AIN_S0T-Pad66)") (class "Default")
      (node (ref "AIN_S0T") (pin "66") (pinfunction "66_66") (pintype "bidirectional"))
      (node (ref "R9") (pin "6") (pinfunction "6_6") (pintype "passive"))
      (node (ref "S9") (pin "11") (pinfunction "11_11") (pintype "passive"))
      (node (ref "U$9") (pin "6") (pinfunction "6_6") (pintype "passive"))
    )
    (net (code "143") (name "Net-(AIN_S0T-Pad67)") (class "Default")
      (node (ref "AIN_S0T") (pin "67") (pinfunction "67_67") (pintype "bidirectional"))
      (node (ref "R9") (pin "7") (pinfunction "7_7") (pintype "passive"))
      (node (ref "S9") (pin "10") (pinfunction "10_10") (pintype "passive"))
      (node (ref "U$9") (pin "7") (pinfunction "7_7") (pintype "passive"))
    )
    (net (code "144") (name "Net-(AIN_S0T-Pad68)") (class "Default")
      (node (ref "AIN_S0T") (pin "68") (pinfunction "68_68") (pintype "bidirectional"))
      (node (ref "R9") (pin "8") (pinfunction "8_8") (pintype "passive"))
      (node (ref "S9") (pin "9") (pinfunction "9_9") (pintype "passive"))
      (node (ref "U$9") (pin "8") (pinfunction "8_8") (pintype "passive"))
    )
    (net (code "145") (name "Net-(GND_IMP-Pad3)") (class "Default")
      (node (ref "GND_IMP") (pin "3") (pinfunction "3_3") (pintype "passive"))
      (node (ref "R_GND") (pin "1") (pinfunction "1_1") (pintype "passive"))
    )
    (net (code "146") (name "Net-(REFA_TO_GND-Pad3)") (class "Default")
      (node (ref "REFA_TO_GND") (pin "3") (pinfunction "3_3") (pintype "passive"))
      (node (ref "R_RA-GND") (pin "1") (pinfunction "1_1") (pintype "passive"))
    )
    (net (code "147") (name "Net-(REFB_TO_GND-Pad3)") (class "Default")
      (node (ref "REFB_TO_GND") (pin "3") (pinfunction "3_3") (pintype "passive"))
      (node (ref "R_RB-GND") (pin "1") (pinfunction "1_1") (pintype "passive"))
    )
    (net (code "148") (name "unconnected-(AIN_N0T-Pad34)") (class "Default")
      (node (ref "AIN_N0T") (pin "34") (pinfunction "34_34") (pintype "bidirectional"))
    )
    (net (code "149") (name "unconnected-(AIN_N0T-Pad35)") (class "Default")
      (node (ref "AIN_N0T") (pin "35") (pinfunction "35_35") (pintype "bidirectional"))
    )
    (net (code "150") (name "unconnected-(AIN_N0T-Pad36)") (class "Default")
      (node (ref "AIN_N0T") (pin "36") (pinfunction "36_36") (pintype "bidirectional"))
    )
    (net (code "151") (name "unconnected-(AIN_N0T-Pad69)") (class "Default")
      (node (ref "AIN_N0T") (pin "69") (pinfunction "69_69") (pintype "bidirectional"))
    )
    (net (code "152") (name "unconnected-(AIN_N0T-Pad70)") (class "Default")
      (node (ref "AIN_N0T") (pin "70") (pinfunction "70_70") (pintype "bidirectional"))
    )
    (net (code "153") (name "unconnected-(AIN_S0T-Pad1)") (class "Default")
      (node (ref "AIN_S0T") (pin "1") (pinfunction "1_1") (pintype "bidirectional"))
    )
    (net (code "154") (name "unconnected-(AIN_S0T-Pad69)") (class "Default")
      (node (ref "AIN_S0T") (pin "69") (pinfunction "69_69") (pintype "bidirectional"))
    )
    (net (code "155") (name "unconnected-(AIN_S0T-Pad70)") (class "Default")
      (node (ref "AIN_S0T") (pin "70") (pinfunction "70_70") (pintype "bidirectional"))
    )
  )
)
